# 3020_V1_1.net
KiCad netlist of a schematic drawn in EasyEDA Pro
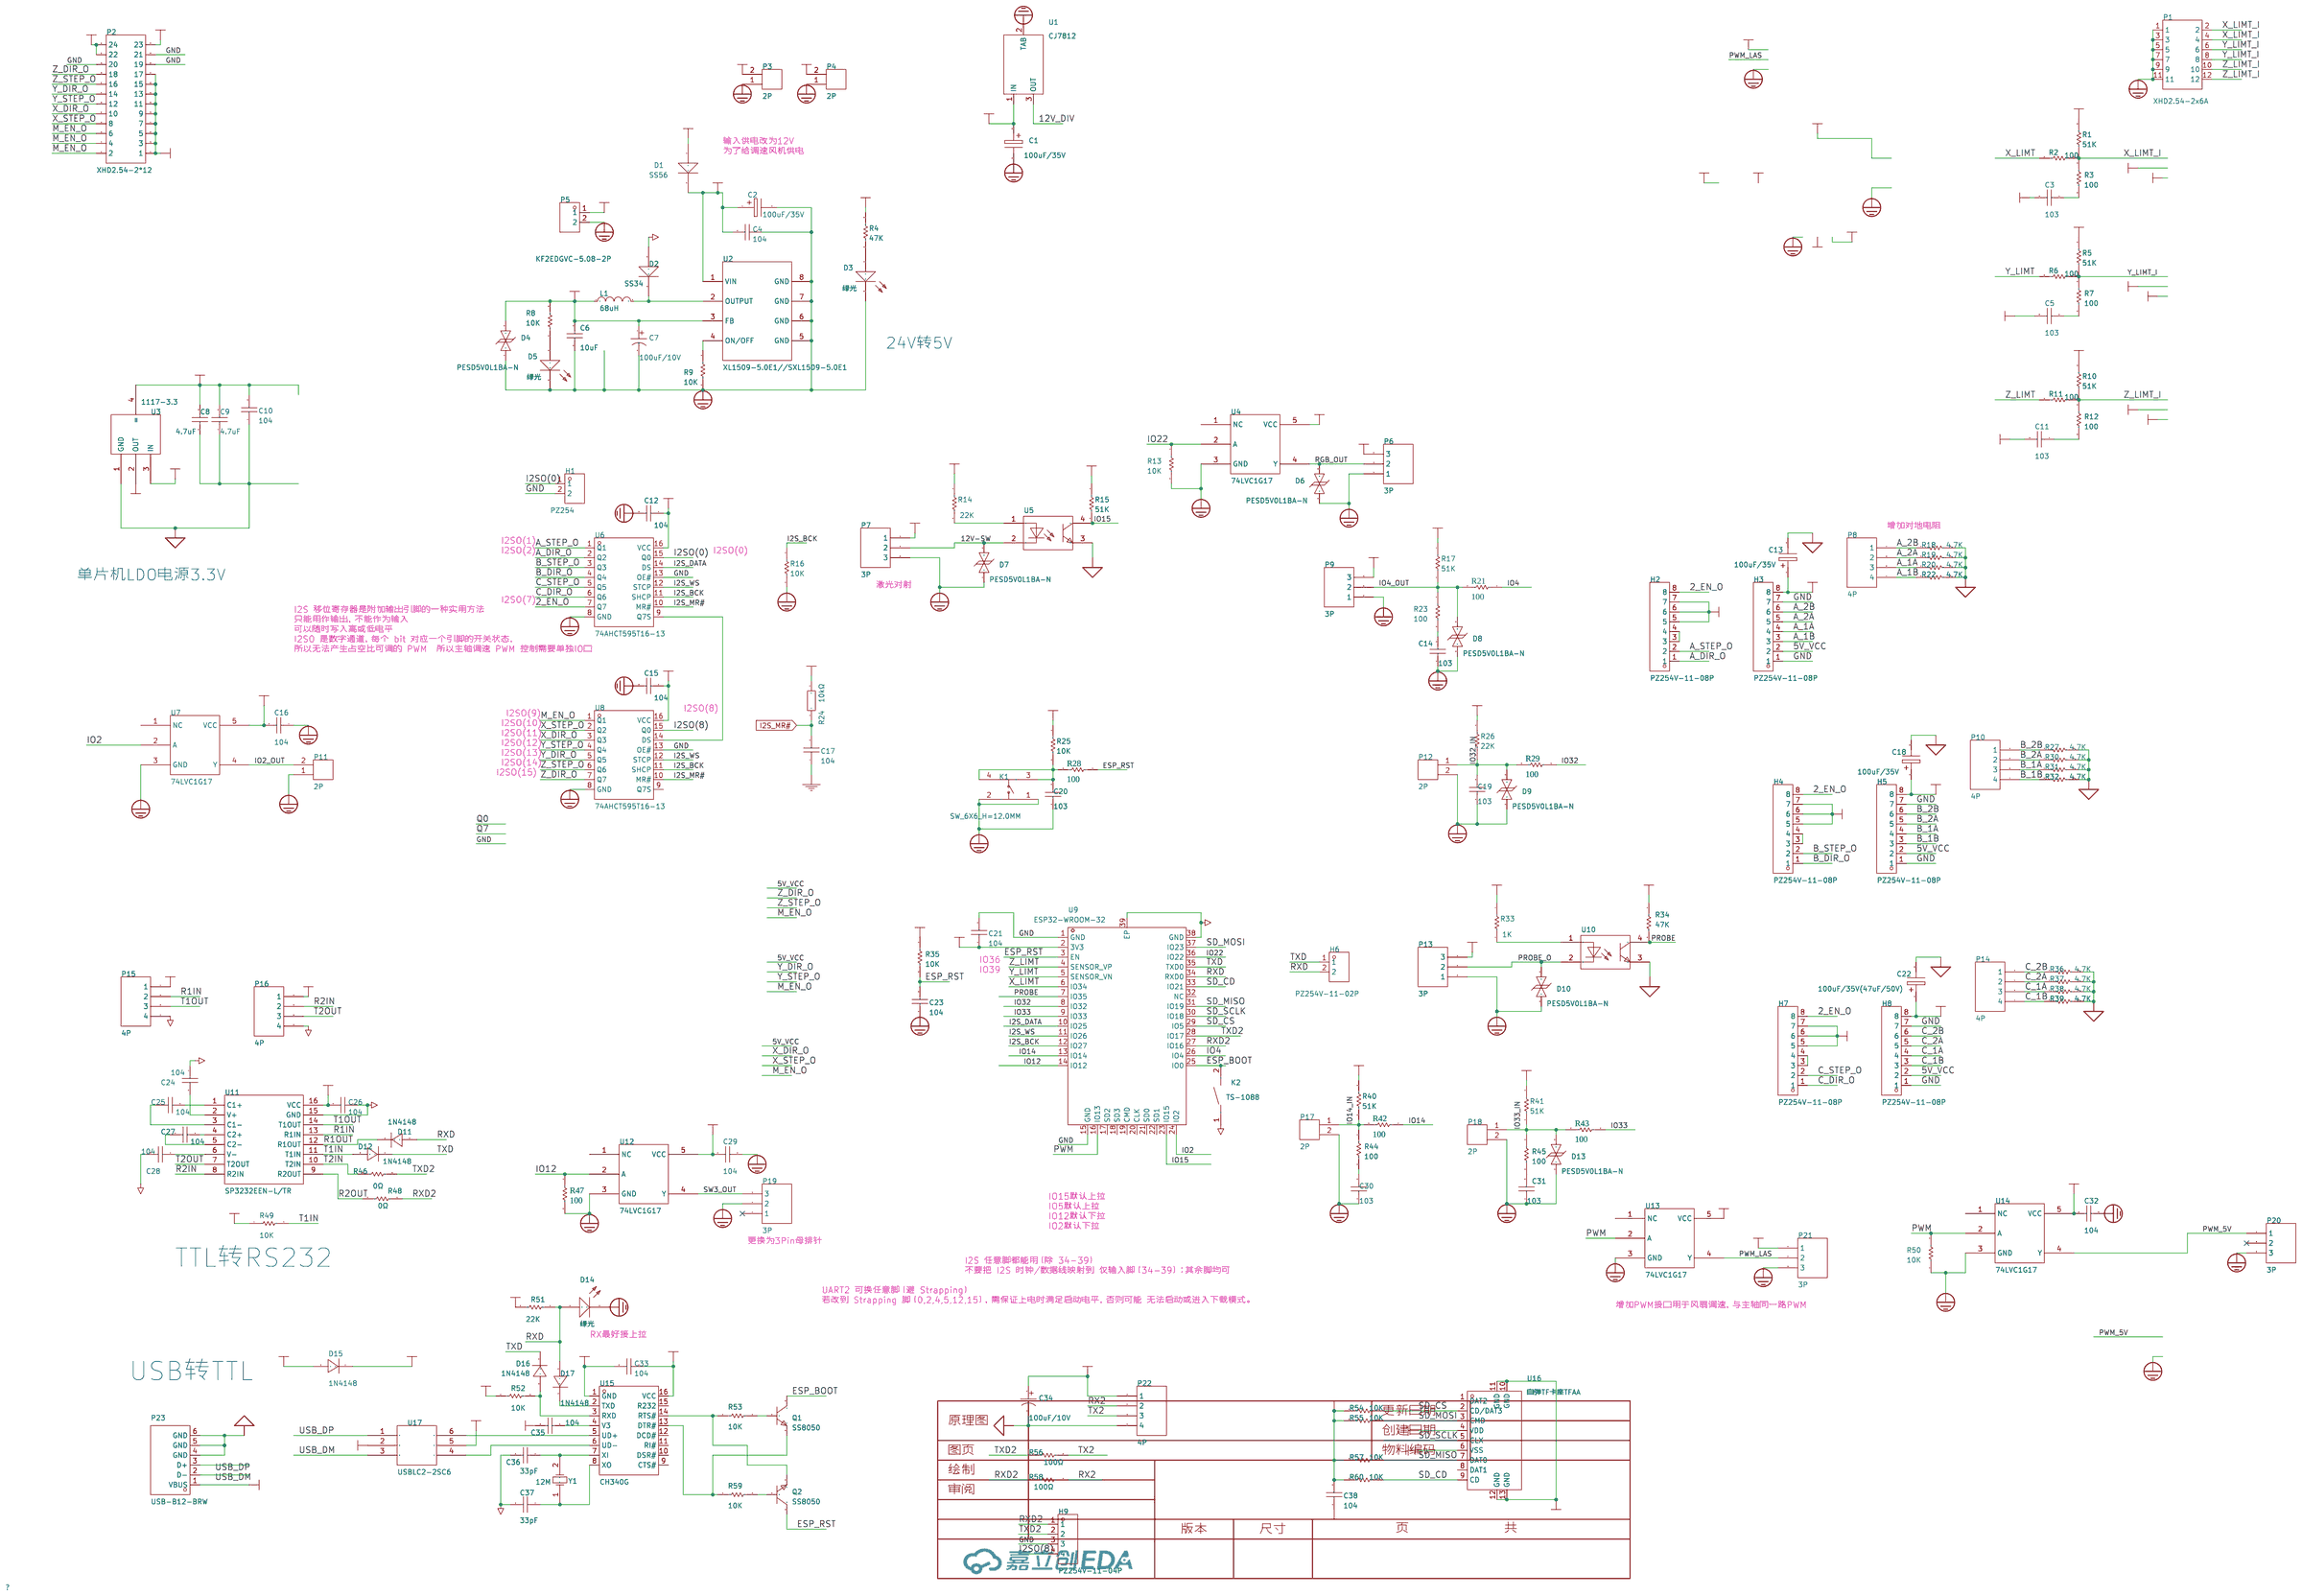
[diagram p0: schematic sheet]

(export (version "E")
  (design (tool "Eeschema 10.0.6"))
  (components
    (comp (ref "C1")
      (value "100uF/35V")
      (footprint "easyedapro:电解电容贴片10x10")
      (libsource (lib "easyedapro") (part "ELECTRO1"))
    )
    (comp (ref "C2")
      (value "100uF/35V")
      (footprint "easyedapro:电解电容贴片10x10")
      (libsource (lib "easyedapro") (part "ELECTRO1"))
    )
    (comp (ref "C3") (value "103") (footprint "easyedapro:11") (libsource (lib "easyedapro") (part "CAP")))
    (comp (ref "C4")
      (value "104")
      (footprint "easyedapro:0603C")
      (description "Capacitor (Semiconductor SIM Model)")
      (libsource (lib "easyedapro") (part "Cap Semi"))
    )
    (comp (ref "C5") (value "103") (footprint "easyedapro:11") (libsource (lib "easyedapro") (part "CAP")))
    (comp (ref "C6") (value "10uF") (libsource (lib "") (part "CAP_1")))
    (comp (ref "C7")
      (value "100uF/10V")
      (footprint "easyedapro:CAP-SMD_BD5.0-L5.3-W5.3-RD")
      (fields (field (name "Manufacturer Part") "CS1A101M-CRD54") (field (name "Manufacturer") "ST(先科)"))
      (libsource (lib "easyedapro") (part "CS1A101M-CRD54"))
    )
    (comp (ref "C8") (value "4.7uF") (libsource (lib "") (part "CAP_1")))
    (comp (ref "C9") (value "4.7uF") (libsource (lib "") (part "CAP_1")))
    (comp (ref "C10")
      (value "104")
      (footprint "easyedapro:0603C")
      (description "Capacitor (Semiconductor SIM Model)")
      (libsource (lib "easyedapro") (part "Cap Semi"))
    )
    (comp (ref "C11") (value "103") (footprint "easyedapro:11") (libsource (lib "easyedapro") (part "CAP")))
    (comp (ref "C12")
      (value "104")
      (footprint "easyedapro:0603C")
      (description "Capacitor (Semiconductor SIM Model)")
      (libsource (lib "easyedapro") (part "Cap Semi"))
    )
    (comp (ref "C13")
      (value "100uF/35V")
      (footprint "easyedapro:电解电容贴片10x10")
      (libsource (lib "easyedapro") (part "ELECTRO1"))
    )
    (comp (ref "C14") (value "103") (footprint "easyedapro:11") (libsource (lib "easyedapro") (part "CAP")))
    (comp (ref "C15")
      (value "104")
      (footprint "easyedapro:0603C")
      (description "Capacitor (Semiconductor SIM Model)")
      (libsource (lib "easyedapro") (part "Cap Semi"))
    )
    (comp (ref "C16")
      (value "104")
      (footprint "easyedapro:0603C")
      (description "Capacitor (Semiconductor SIM Model)")
      (libsource (lib "easyedapro") (part "Cap Semi"))
    )
    (comp (ref "C17")
      (value "104")
      (footprint "easyedapro:0603C")
      (description "Capacitor (Semiconductor SIM Model)")
      (libsource (lib "easyedapro") (part "Cap Semi"))
    )
    (comp (ref "C18")
      (value "100uF/35V")
      (footprint "easyedapro:电解电容贴片10x10")
      (libsource (lib "easyedapro") (part "ELECTRO1"))
    )
    (comp (ref "C19") (value "103") (footprint "easyedapro:11") (libsource (lib "easyedapro") (part "CAP")))
    (comp (ref "C20") (value "103") (footprint "easyedapro:11") (libsource (lib "easyedapro") (part "CAP")))
    (comp (ref "C21")
      (value "104")
      (footprint "easyedapro:0603C")
      (description "Capacitor (Semiconductor SIM Model)")
      (libsource (lib "easyedapro") (part "Cap Semi"))
    )
    (comp (ref "C22")
      (value "100uF/35V(47uF/50V)")
      (footprint "easyedapro:电解电容贴片10x10")
      (libsource (lib "easyedapro") (part "ELECTRO1"))
    )
    (comp (ref "C23")
      (value "104")
      (footprint "easyedapro:0603C")
      (description "Capacitor (Semiconductor SIM Model)")
      (libsource (lib "easyedapro") (part "Cap Semi"))
    )
    (comp (ref "C24")
      (value "104")
      (footprint "easyedapro:0603C")
      (description "Capacitor (Semiconductor SIM Model)")
      (libsource (lib "easyedapro") (part "Cap Semi"))
    )
    (comp (ref "C25")
      (value "104")
      (footprint "easyedapro:0603C")
      (description "Capacitor (Semiconductor SIM Model)")
      (libsource (lib "easyedapro") (part "Cap Semi"))
    )
    (comp (ref "C26")
      (value "104")
      (footprint "easyedapro:0603C")
      (description "Capacitor (Semiconductor SIM Model)")
      (libsource (lib "easyedapro") (part "Cap Semi"))
    )
    (comp (ref "C27")
      (value "104")
      (footprint "easyedapro:0603C")
      (description "Capacitor (Semiconductor SIM Model)")
      (libsource (lib "easyedapro") (part "Cap Semi"))
    )
    (comp (ref "C28")
      (value "104")
      (footprint "easyedapro:0603C")
      (description "Capacitor (Semiconductor SIM Model)")
      (libsource (lib "easyedapro") (part "Cap Semi"))
    )
    (comp (ref "C29")
      (value "104")
      (footprint "easyedapro:0603C")
      (description "Capacitor (Semiconductor SIM Model)")
      (libsource (lib "easyedapro") (part "Cap Semi"))
    )
    (comp (ref "C30") (value "103") (footprint "easyedapro:11") (libsource (lib "easyedapro") (part "CAP")))
    (comp (ref "C31") (value "103") (footprint "easyedapro:11") (libsource (lib "easyedapro") (part "CAP")))
    (comp (ref "C32")
      (value "104")
      (footprint "easyedapro:0603C")
      (description "Capacitor (Semiconductor SIM Model)")
      (libsource (lib "easyedapro") (part "Cap Semi"))
    )
    (comp (ref "C33")
      (value "104")
      (footprint "easyedapro:0603C")
      (description "Capacitor (Semiconductor SIM Model)")
      (libsource (lib "easyedapro") (part "Cap Semi"))
    )
    (comp (ref "C34")
      (value "100uF/10V")
      (footprint "easyedapro:CAP-SMD_BD5.0-L5.3-W5.3-RD")
      (fields (field (name "Manufacturer Part") "CS1A101M-CRD54") (field (name "Manufacturer") "ST(先科)"))
      (libsource (lib "easyedapro") (part "CS1A101M-CRD54"))
    )
    (comp (ref "C35")
      (value "104")
      (footprint "easyedapro:0603C")
      (description "Capacitor (Semiconductor SIM Model)")
      (libsource (lib "easyedapro") (part "Cap Semi"))
    )
    (comp (ref "C36")
      (value "18pF")
      (footprint "easyedapro:0603C")
      (description "Capacitor (Semiconductor SIM Model)")
      (libsource (lib "easyedapro") (part "Cap Semi"))
    )
    (comp (ref "C37")
      (value "18pF")
      (footprint "easyedapro:0603C")
      (description "Capacitor (Semiconductor SIM Model)")
      (libsource (lib "easyedapro") (part "Cap Semi"))
    )
    (comp (ref "C38")
      (value "104")
      (footprint "easyedapro:11")
      (description "Capacitor (Semiconductor SIM Model)")
      (libsource (lib "easyedapro") (part "Cap Semi"))
    )
    (comp (ref "D1") (value "SS56") (footprint "easyedapro:SMA") (libsource (lib "") (part "1N4148_1")))
    (comp (ref "D2") (value "SS34") (libsource (lib "easyedapro") (part "1N4148")))
    (comp (ref "D3")
      (value "绿光")
      (footprint "easyedapro:0603LED")
      (libsource (lib "easyedapro") (part "LED"))
    )
    (comp (ref "D4")
      (value "PESD5V0L1BA-N")
      (footprint "easyedapro:SOD-523_L1.2-W0.8-LS1.6-BI")
      (description "极性:Bidirectional;反向关断电压（典型值）:5V (Max);击穿电压（最小值）:6V;箝位电压:15V;峰值脉冲电流（10/1000us）:5A (8/20us);")
      (fields (field (name "Manufacturer") "BORN伯恩半导体"))
      (libsource (lib "easyedapro") (part "PESD5V0S1BBN"))
    )
    (comp (ref "D5")
      (value "绿光")
      (footprint "easyedapro:0603LED")
      (libsource (lib "easyedapro") (part "LED"))
    )
    (comp (ref "D6")
      (value "PESD5V0L1BA-N")
      (footprint "easyedapro:SOD-523_L1.2-W0.8-LS1.6-BI")
      (description "极性:Bidirectional;反向关断电压（典型值）:5V (Max);击穿电压（最小值）:6V;箝位电压:15V;峰值脉冲电流（10/1000us）:5A (8/20us);")
      (fields (field (name "Manufacturer") "BORN伯恩半导体"))
      (libsource (lib "easyedapro") (part "PESD5V0S1BBN"))
    )
    (comp (ref "D7")
      (value "PESD5V0L1BA-N")
      (footprint "easyedapro:SOD-523_L1.2-W0.8-LS1.6-BI")
      (description "极性:Bidirectional;反向关断电压（典型值）:5V (Max);击穿电压（最小值）:6V;箝位电压:15V;峰值脉冲电流（10/1000us）:5A (8/20us);")
      (fields (field (name "Manufacturer") "BORN伯恩半导体"))
      (libsource (lib "easyedapro") (part "PESD5V0S1BBN"))
    )
    (comp (ref "D8")
      (value "PESD5V0L1BA-N")
      (footprint "easyedapro:SOD-523_L1.2-W0.8-LS1.6-BI")
      (description "极性:Bidirectional;反向关断电压（典型值）:5V (Max);击穿电压（最小值）:6V;箝位电压:15V;峰值脉冲电流（10/1000us）:5A (8/20us);")
      (fields (field (name "Manufacturer") "BORN伯恩半导体"))
      (libsource (lib "easyedapro") (part "PESD5V0S1BBN"))
    )
    (comp (ref "D9")
      (value "PESD5V0L1BA-N")
      (footprint "easyedapro:SOD-523_L1.2-W0.8-LS1.6-BI")
      (description "极性:Bidirectional;反向关断电压（典型值）:5V (Max);击穿电压（最小值）:6V;箝位电压:15V;峰值脉冲电流（10/1000us）:5A (8/20us);")
      (fields (field (name "Manufacturer") "BORN伯恩半导体"))
      (libsource (lib "easyedapro") (part "PESD5V0S1BBN"))
    )
    (comp (ref "D10")
      (value "PESD5V0L1BA-N")
      (footprint "easyedapro:SOD-523_L1.2-W0.8-LS1.6-BI")
      (description "极性:Bidirectional;反向关断电压（典型值）:5V (Max);击穿电压（最小值）:6V;箝位电压:15V;峰值脉冲电流（10/1000us）:5A (8/20us);")
      (fields (field (name "Manufacturer") "BORN伯恩半导体"))
      (libsource (lib "easyedapro") (part "PESD5V0S1BBN"))
    )
    (comp (ref "D11")
      (value "1N4148")
      (footprint "easyedapro:SOD-123_L2.8-W1.8-LS3.7-RD")
      (fields (field (name "Manufacturer") "VISHAY(威世)"))
      (libsource (lib "easyedapro") (part "1N4148W-E3-08"))
    )
    (comp (ref "D12")
      (value "1N4148")
      (footprint "easyedapro:SOD-123_L2.8-W1.8-LS3.7-RD")
      (fields (field (name "Manufacturer") "VISHAY(威世)"))
      (libsource (lib "easyedapro") (part "1N4148W-E3-08"))
    )
    (comp (ref "D13")
      (value "PESD5V0L1BA-N")
      (footprint "easyedapro:SOD-523_L1.2-W0.8-LS1.6-BI")
      (description "极性:Bidirectional;反向关断电压（典型值）:5V (Max);击穿电压（最小值）:6V;箝位电压:15V;峰值脉冲电流（10/1000us）:5A (8/20us);")
      (fields (field (name "Manufacturer") "BORN伯恩半导体"))
      (libsource (lib "easyedapro") (part "PESD5V0S1BBN"))
    )
    (comp (ref "D14")
      (value "绿光")
      (footprint "easyedapro:0603LED")
      (libsource (lib "easyedapro") (part "LED"))
    )
    (comp (ref "D15")
      (value "1N4148")
      (footprint "easyedapro:SOD-123_L2.8-W1.8-LS3.7-RD")
      (fields (field (name "Manufacturer") "VISHAY(威世)"))
      (libsource (lib "easyedapro") (part "1N4148W-E3-08"))
    )
    (comp (ref "D16")
      (value "1N4148")
      (footprint "easyedapro:SOD-123_L2.8-W1.8-LS3.7-RD")
      (fields (field (name "Manufacturer") "VISHAY(威世)"))
      (libsource (lib "easyedapro") (part "1N4148W-E3-08"))
    )
    (comp (ref "D17")
      (value "1N4148")
      (footprint "easyedapro:SOD-123_L2.8-W1.8-LS3.7-RD")
      (fields (field (name "Manufacturer") "VISHAY(威世)"))
      (libsource (lib "easyedapro") (part "1N4148W-E3-08"))
    )
    (comp (ref "H1")
      (value "PZ254")
      (footprint "easyedapro:HDR-TH_2P-P2.54-V-M")
      (fields (field (name "Manufacturer") "XFCN(兴飞)"))
      (libsource (lib "easyedapro") (part "PZ254V-11-02P"))
    )
    (comp (ref "H2")
      (value "PZ254V-11-08P")
      (footprint "easyedapro:HDR-TH_8P-P2.54-V-M")
      (fields (field (name "Manufacturer") "XFCN(兴飞)"))
      (libsource (lib "easyedapro") (part "PZ254V-11-08P"))
    )
    (comp (ref "H3")
      (value "PZ254V-11-08P")
      (footprint "easyedapro:HDR-TH_8P-P2.54-V-M")
      (fields (field (name "Manufacturer") "XFCN(兴飞)"))
      (libsource (lib "easyedapro") (part "PZ254V-11-08P"))
    )
    (comp (ref "H4")
      (value "PZ254V-11-08P")
      (footprint "easyedapro:HDR-TH_8P-P2.54-V-M")
      (fields (field (name "Manufacturer") "XFCN(兴飞)"))
      (libsource (lib "easyedapro") (part "PZ254V-11-08P"))
    )
    (comp (ref "H5")
      (value "PZ254V-11-08P")
      (footprint "easyedapro:HDR-TH_8P-P2.54-V-M")
      (fields (field (name "Manufacturer") "XFCN(兴飞)"))
      (libsource (lib "easyedapro") (part "PZ254V-11-08P"))
    )
    (comp (ref "H6")
      (value "PZ254V-11-02P")
      (footprint "easyedapro:HDR-TH_2P-P2.54-V-M")
      (fields (field (name "Manufacturer") "XFCN(兴飞)"))
      (libsource (lib "easyedapro") (part "PZ254V-11-02P"))
    )
    (comp (ref "H7")
      (value "PZ254V-11-08P")
      (footprint "easyedapro:HDR-TH_8P-P2.54-V-M")
      (fields (field (name "Manufacturer") "XFCN(兴飞)"))
      (libsource (lib "easyedapro") (part "PZ254V-11-08P"))
    )
    (comp (ref "H8")
      (value "PZ254V-11-08P")
      (footprint "easyedapro:HDR-TH_8P-P2.54-V-M")
      (fields (field (name "Manufacturer") "XFCN(兴飞)"))
      (libsource (lib "easyedapro") (part "PZ254V-11-08P"))
    )
    (comp (ref "H9")
      (value "PZ254V-11-04P")
      (footprint "easyedapro:HDR-TH_4P-P2.54-V-M")
      (fields (field (name "Manufacturer") "XFCN(兴飞)"))
      (libsource (lib "easyedapro") (part "PZ254V-11-04P_C2691448"))
    )
    (comp (ref "K1")
      (value "SW_6X6_H=12.0MM")
      (footprint "easyedapro:KEY-SMD_4P-L6.0-W6.0-P4.50-LS9.0")
      (libsource (lib "easyedapro") (part "SW_6X6_H=12.0MM"))
    )
    (comp (ref "K2")
      (value "TS-1088")
      (footprint "easyedapro:SW-SMD_L3.9-W3.0-P4.45")
      (fields (field (name "Manufacturer") "XUNPU(讯普)"))
      (libsource (lib "easyedapro") (part "TS-1088-AR02016"))
    )
    (comp (ref "L1")
      (value "68uH")
      (footprint "easyedapro:IND-SMD_L7.0-W7.0_SMDRI74-330MT")
      (description "电感值:33uH;精度:±20%;额定电流:960mA;饱和电流(Isat):1.8A;类型:屏蔽电感;")
      (fields (field (name "Manufacturer Part") "SMDRI74-330MT") (field (name "Manufacturer") "SXN(顺翔诺)"))
      (libsource (lib "easyedapro") (part "SMDRI74-330MT"))
    )
    (comp (ref "P1")
      (value "XHD2.54-2x6A")
      (footprint "easyedapro:CONN-TH_12P-P2.50_HC-XHD2.54-2X6A")
      (fields (field (name "Manufacturer") "HC(虹成电子)"))
      (libsource (lib "easyedapro") (part "HC-XHD2.54-2X6A"))
    )
    (comp (ref "P2")
      (value "XHD2.54-2*12")
      (footprint "easyedapro:IDC-TH_24P-P2.54-V-R2-C12-S2.54")
      (fields (field (name "Manufacturer") "BOOMELE(博穆精密)"))
      (libsource (lib "easyedapro") (part "HDR-IDC-2.54-2X12P"))
    )
    (comp (ref "P3") (value "2P") (libsource (lib "easyedapro") (part "2P")))
    (comp (ref "P4") (value "2P") (libsource (lib "easyedapro") (part "2P")))
    (comp (ref "P5")
      (value "KF2EDGVC-5.08-2P")
      (footprint "easyedapro:CONN-TH_P5.08_KF2EDGVC-5.08-2P")
      (description "连接器类型:板端/插座-闭口;结构:1x2P;间距:5.08mm;颜色:绿色;安装方式:直针;排数:1;每排PIN数:2;额定电流:15A;额定电压:300V;工作温度:-40°C~+105°C;")
      (fields (field (name "Manufacturer") "KEFA(科发)"))
      (libsource (lib "easyedapro") (part "KF2EDGVC-5.08-2P"))
    )
    (comp (ref "P6")
      (value "3P")
      (footprint "easyedapro:HDR1X3_CON")
      (libsource (lib "easyedapro") (part "3P"))
    )
    (comp (ref "P7")
      (value "3P")
      (footprint "easyedapro:HDR1X3_CON")
      (libsource (lib "easyedapro") (part "3P"))
    )
    (comp (ref "P8")
      (value "4P")
      (footprint "easyedapro:HDR1X4_CON")
      (libsource (lib "easyedapro") (part "4P"))
    )
    (comp (ref "P9")
      (value "3P")
      (footprint "easyedapro:HDR1X3_CON")
      (libsource (lib "easyedapro") (part "3P"))
    )
    (comp (ref "P10")
      (value "4P")
      (footprint "easyedapro:HDR1X4_CON")
      (libsource (lib "easyedapro") (part "4P"))
    )
    (comp (ref "P11") (value "2P") (libsource (lib "easyedapro") (part "2P")))
    (comp (ref "P12") (value "2P") (libsource (lib "easyedapro") (part "2P")))
    (comp (ref "P13")
      (value "3P")
      (footprint "easyedapro:HDR1X3_CON")
      (libsource (lib "easyedapro") (part "3P"))
    )
    (comp (ref "P14")
      (value "4P")
      (footprint "easyedapro:HDR1X4_CON")
      (libsource (lib "easyedapro") (part "4P"))
    )
    (comp (ref "P15")
      (value "4P")
      (footprint "easyedapro:HDR1X4_CON")
      (libsource (lib "easyedapro") (part "4P"))
    )
    (comp (ref "P16")
      (value "4P")
      (footprint "easyedapro:HDR1X4_CON")
      (libsource (lib "easyedapro") (part "4P"))
    )
    (comp (ref "P17") (value "2P") (libsource (lib "easyedapro") (part "2P")))
    (comp (ref "P18") (value "2P") (libsource (lib "easyedapro") (part "2P")))
    (comp (ref "P19")
      (value "3P")
      (footprint "easyedapro:HDR1X3_CON")
      (libsource (lib "easyedapro") (part "3P"))
    )
    (comp (ref "P20")
      (value "3P")
      (footprint "easyedapro:HDR1X3_CON")
      (libsource (lib "easyedapro") (part "3P"))
    )
    (comp (ref "P21")
      (value "3P")
      (footprint "easyedapro:HDR1X3_CON")
      (libsource (lib "easyedapro") (part "3P"))
    )
    (comp (ref "P22")
      (value "4P")
      (footprint "easyedapro:HDR1X4_CON")
      (libsource (lib "easyedapro") (part "4P"))
    )
    (comp (ref "P23")
      (value "USB-B12-BRW")
      (footprint "easyedapro:USB-B-TH_USB-B12-BRW")
      (description "连接器类型:Type-B;协议标准:USB 2.0;公母:母;安装方式:直插;触点数量:4P;端口数量:1;额定电流 - 电源:1.5A;工作温度:-20°C~+70°C;")
      (fields (field (name "Manufacturer") "XUNPU(讯普)"))
      (libsource (lib "easyedapro") (part "USB-B12-BRW"))
    )
    (comp (ref "Q1")
      (value "SS8050")
      (footprint "easyedapro:SOT-23-3_L2.9-W1.3-P1.90-LS2.4-BR")
      (fields (field (name "Manufacturer") "Doeshare(德芯)"))
      (libsource (lib "easyedapro") (part "SS8050_C2931717"))
    )
    (comp (ref "Q2")
      (value "SS8050")
      (footprint "easyedapro:SOT-23-3_L2.9-W1.3-P1.90-LS2.4-BR")
      (fields (field (name "Manufacturer") "Doeshare(德芯)"))
      (libsource (lib "easyedapro") (part "SS8050_C2931717"))
    )
    (comp (ref "R1")
      (value "51K")
      (footprint "easyedapro:10")
      (description "Resistor")
      (libsource (lib "easyedapro") (part "RES"))
    )
    (comp (ref "R2")
      (value "100")
      (footprint "easyedapro:10")
      (description "Resistor")
      (libsource (lib "easyedapro") (part "RES"))
    )
    (comp (ref "R3")
      (value "100")
      (footprint "easyedapro:10")
      (description "Resistor")
      (libsource (lib "easyedapro") (part "RES"))
    )
    (comp (ref "R4")
      (value "47K")
      (footprint "easyedapro:0603R")
      (description "Resistor")
      (libsource (lib "easyedapro") (part "RES"))
    )
    (comp (ref "R5")
      (value "51K")
      (footprint "easyedapro:10")
      (description "Resistor")
      (libsource (lib "easyedapro") (part "RES"))
    )
    (comp (ref "R6")
      (value "100")
      (footprint "easyedapro:10")
      (description "Resistor")
      (libsource (lib "easyedapro") (part "RES"))
    )
    (comp (ref "R7")
      (value "100")
      (footprint "easyedapro:10")
      (description "Resistor")
      (libsource (lib "easyedapro") (part "RES"))
    )
    (comp (ref "R8")
      (value "10K")
      (footprint "easyedapro:0603R")
      (description "Resistor")
      (libsource (lib "easyedapro") (part "RES"))
    )
    (comp (ref "R9")
      (value "10K")
      (footprint "easyedapro:0603R")
      (description "Resistor")
      (libsource (lib "easyedapro") (part "RES"))
    )
    (comp (ref "R10")
      (value "51K")
      (footprint "easyedapro:10")
      (description "Resistor")
      (libsource (lib "easyedapro") (part "RES"))
    )
    (comp (ref "R11")
      (value "100")
      (footprint "easyedapro:10")
      (description "Resistor")
      (libsource (lib "easyedapro") (part "RES"))
    )
    (comp (ref "R12")
      (value "100")
      (footprint "easyedapro:10")
      (description "Resistor")
      (libsource (lib "easyedapro") (part "RES"))
    )
    (comp (ref "R13")
      (value "10K")
      (description "Resistor")
      (fields (field (name "Publisher") "Altium Limited"))
      (libsource (lib "") (part "RES_1"))
    )
    (comp (ref "R14")
      (value "22K")
      (footprint "easyedapro:0603R")
      (description "Resistor")
      (libsource (lib "easyedapro") (part "RES"))
    )
    (comp (ref "R15")
      (value "10K")
      (footprint "easyedapro:0603R")
      (description "Resistor")
      (libsource (lib "easyedapro") (part "RES"))
    )
    (comp (ref "R16")
      (value "10K")
      (footprint "easyedapro:0603R")
      (description "Resistor")
      (libsource (lib "easyedapro") (part "RES"))
    )
    (comp (ref "R17")
      (value "10K")
      (footprint "easyedapro:0603R")
      (description "Resistor")
      (libsource (lib "easyedapro") (part "RES"))
    )
    (comp (ref "R18")
      (value "10K")
      (footprint "easyedapro:0603R")
      (description "Resistor")
      (libsource (lib "easyedapro") (part "10K"))
    )
    (comp (ref "R19")
      (value "10K")
      (footprint "easyedapro:0603R")
      (description "Resistor")
      (libsource (lib "easyedapro") (part "10K"))
    )
    (comp (ref "R20")
      (value "10K")
      (footprint "easyedapro:0603R")
      (description "Resistor")
      (libsource (lib "easyedapro") (part "10K"))
    )
    (comp (ref "R21")
      (value "100")
      (description "Resistor")
      (fields (field (name "Publisher") "Altium Limited"))
      (libsource (lib "") (part "RES_1"))
    )
    (comp (ref "R22")
      (value "10K")
      (footprint "easyedapro:0603R")
      (description "Resistor")
      (libsource (lib "easyedapro") (part "10K"))
    )
    (comp (ref "R23")
      (value "100")
      (footprint "easyedapro:10")
      (description "Resistor")
      (libsource (lib "easyedapro") (part "RES"))
    )
    (comp (ref "R24")
      (value "10kΩ")
      (footprint "easyedapro:R0603")
      (fields (field (name "Manufacturer Part") "0603WAF1002T5E") (field (name "Manufacturer") "UniOhm"))
      (libsource (lib "easyedapro") (part "10kΩ"))
    )
    (comp (ref "R25")
      (value "10K")
      (footprint "easyedapro:0603R")
      (description "Resistor")
      (libsource (lib "easyedapro") (part "RES"))
    )
    (comp (ref "R26")
      (value "10K")
      (footprint "easyedapro:0603R")
      (description "Resistor")
      (libsource (lib "easyedapro") (part "RES"))
    )
    (comp (ref "R27")
      (value "10K")
      (footprint "easyedapro:0603R")
      (description "Resistor")
      (libsource (lib "easyedapro") (part "10K"))
    )
    (comp (ref "R28")
      (value "100")
      (description "Resistor")
      (fields (field (name "Publisher") "Altium Limited"))
      (libsource (lib "") (part "RES_1"))
    )
    (comp (ref "R29")
      (value "100")
      (description "Resistor")
      (fields (field (name "Publisher") "Altium Limited"))
      (libsource (lib "") (part "RES_1"))
    )
    (comp (ref "R30")
      (value "10K")
      (footprint "easyedapro:0603R")
      (description "Resistor")
      (libsource (lib "easyedapro") (part "10K"))
    )
    (comp (ref "R31")
      (value "10K")
      (footprint "easyedapro:0603R")
      (description "Resistor")
      (libsource (lib "easyedapro") (part "10K"))
    )
    (comp (ref "R32")
      (value "10K")
      (footprint "easyedapro:0603R")
      (description "Resistor")
      (libsource (lib "easyedapro") (part "10K"))
    )
    (comp (ref "R33")
      (value "1K")
      (footprint "easyedapro:0603R")
      (description "Resistor")
      (libsource (lib "easyedapro") (part "RES"))
    )
    (comp (ref "R34")
      (value "10K")
      (footprint "easyedapro:0603R")
      (description "Resistor")
      (libsource (lib "easyedapro") (part "RES"))
    )
    (comp (ref "R35")
      (value "10K")
      (footprint "easyedapro:0603R")
      (description "Resistor")
      (libsource (lib "easyedapro") (part "RES"))
    )
    (comp (ref "R36")
      (value "10K")
      (footprint "easyedapro:0603R")
      (description "Resistor")
      (libsource (lib "easyedapro") (part "10K"))
    )
    (comp (ref "R37")
      (value "10K")
      (footprint "easyedapro:0603R")
      (description "Resistor")
      (libsource (lib "easyedapro") (part "10K"))
    )
    (comp (ref "R38")
      (value "10K")
      (footprint "easyedapro:0603R")
      (description "Resistor")
      (libsource (lib "easyedapro") (part "10K"))
    )
    (comp (ref "R39")
      (value "10K")
      (footprint "easyedapro:0603R")
      (description "Resistor")
      (libsource (lib "easyedapro") (part "10K"))
    )
    (comp (ref "R40")
      (value "10K")
      (footprint "easyedapro:0603R")
      (description "Resistor")
      (libsource (lib "easyedapro") (part "RES"))
    )
    (comp (ref "R41")
      (value "10K")
      (footprint "easyedapro:0603R")
      (description "Resistor")
      (libsource (lib "easyedapro") (part "RES"))
    )
    (comp (ref "R42")
      (value "100")
      (description "Resistor")
      (fields (field (name "Publisher") "Altium Limited"))
      (libsource (lib "") (part "RES_1"))
    )
    (comp (ref "R43")
      (value "100")
      (description "Resistor")
      (fields (field (name "Publisher") "Altium Limited"))
      (libsource (lib "") (part "RES_1"))
    )
    (comp (ref "R44")
      (value "100")
      (footprint "easyedapro:10")
      (description "Resistor")
      (libsource (lib "easyedapro") (part "RES"))
    )
    (comp (ref "R45")
      (value "100")
      (footprint "easyedapro:10")
      (description "Resistor")
      (libsource (lib "easyedapro") (part "RES"))
    )
    (comp (ref "R46")
      (value "0Ω")
      (footprint "easyedapro:0603R")
      (description "Resistor")
      (libsource (lib "easyedapro") (part "RES"))
    )
    (comp (ref "R47")
      (value "100")
      (description "Resistor")
      (fields (field (name "Publisher") "Altium Limited"))
      (libsource (lib "") (part "RES_1"))
    )
    (comp (ref "R48")
      (value "0Ω")
      (footprint "easyedapro:0603R")
      (description "Resistor")
      (libsource (lib "easyedapro") (part "RES"))
    )
    (comp (ref "R49")
      (value "10K")
      (footprint "easyedapro:0603R")
      (description "Resistor")
      (libsource (lib "easyedapro") (part "RES"))
    )
    (comp (ref "R50")
      (value "10K")
      (description "Resistor")
      (fields (field (name "Publisher") "Altium Limited"))
      (libsource (lib "") (part "RES_1"))
    )
    (comp (ref "R51")
      (value "10K")
      (footprint "easyedapro:0603R")
      (description "Resistor")
      (libsource (lib "easyedapro") (part "RES"))
    )
    (comp (ref "R52")
      (value "10K")
      (footprint "easyedapro:0603R")
      (description "Resistor")
      (libsource (lib "easyedapro") (part "RES"))
    )
    (comp (ref "R53")
      (value "10K")
      (footprint "easyedapro:0603R")
      (description "Resistor")
      (libsource (lib "easyedapro") (part "RES"))
    )
    (comp (ref "R54")
      (value "10K")
      (footprint "easyedapro:10")
      (description "Resistor")
      (libsource (lib "easyedapro") (part "RES"))
    )
    (comp (ref "R55")
      (value "10K")
      (footprint "easyedapro:10")
      (description "Resistor")
      (libsource (lib "easyedapro") (part "RES"))
    )
    (comp (ref "R56")
      (value "100Ω")
      (footprint "easyedapro:0603R")
      (description "Resistor")
      (libsource (lib "easyedapro") (part "RES"))
    )
    (comp (ref "R57")
      (value "10K")
      (footprint "easyedapro:10")
      (description "Resistor")
      (libsource (lib "easyedapro") (part "RES"))
    )
    (comp (ref "R58")
      (value "100Ω")
      (footprint "easyedapro:0603R")
      (description "Resistor")
      (libsource (lib "easyedapro") (part "RES"))
    )
    (comp (ref "R59")
      (value "10K")
      (footprint "easyedapro:0603R")
      (description "Resistor")
      (libsource (lib "easyedapro") (part "RES"))
    )
    (comp (ref "R60")
      (value "10K")
      (footprint "easyedapro:10")
      (description "Resistor")
      (libsource (lib "easyedapro") (part "RES"))
    )
    (comp (ref "U1")
      (value "CJ7812")
      (footprint "easyedapro:TO-263-2_L10.1-W9.1-P5.08-LS15.2-TL")
      (description "输出类型:固定;工作电压:35V;输出电压:12V;输出电流:1.5A;电源纹波抑制比(PSRR):71dB@(120Hz);输出极性:正极;")
      (fields (field (name "Manufacturer") "CJ(江苏长电/长晶)"))
      (libsource (lib "easyedapro") (part "CJ7812_C145151"))
    )
    (comp (ref "U2")
      (value "XL1509-5.0E1//SXL1509-5.0E1")
      (footprint "easyedapro:SOIC-8_L5.0-W4.0-P1.27-LS6.0-BL")
      (description "功能类型:降压型;同步整流:-;输出通道数:-;拓扑结构:-;输入电压:-;输出电流(最大值):-;开关频率:-;")
      (fields (field (name "Manufacturer") "XLSEMI(芯龙)"))
      (libsource (lib "easyedapro") (part "XL1509-5.0E1"))
    )
    (comp (ref "U3")
      (value "1117-3.3")
      (footprint "easyedapro:SOT-223")
      (libsource (lib "easyedapro") (part "LM1117"))
    )
    (comp (ref "U4")
      (value "74LVC1G17")
      (footprint "easyedapro:SMD8")
      (libsource (lib "easyedapro") (part "74LVC1G04"))
    )
    (comp (ref "U5")
      (value "LTV-357T-C")
      (footprint "easyedapro:SOP-4_L4.4-W3.9-P2.54-LS7.0-TL")
      (fields (field (name "Manufacturer") "LITEON(光宝)"))
      (libsource (lib "easyedapro") (part "LTV-357T-C"))
    )
    (comp (ref "U6")
      (value "74AHCT595T16-13")
      (footprint "easyedapro:TSSOP-16_L5.0-W4.4-P0.65-LS6.4-BL")
      (description "功能:串行至串行或并行;工作电压:4.5V~5.5V;元件数:1;每个元件位数:8;")
      (fields (field (name "Manufacturer") "DIODES(美台)"))
      (libsource (lib "easyedapro") (part "74AHCT595T16-13"))
    )
    (comp (ref "U7")
      (value "74LVC1G17")
      (footprint "easyedapro:SMD8")
      (libsource (lib "easyedapro") (part "74LVC1G04"))
    )
    (comp (ref "U8")
      (value "74AHCT595T16-13")
      (footprint "easyedapro:TSSOP-16_L5.0-W4.4-P0.65-LS6.4-BL")
      (description "功能:串行至串行或并行;工作电压:4.5V~5.5V;元件数:1;每个元件位数:8;")
      (fields (field (name "Manufacturer") "DIODES(美台)"))
      (libsource (lib "easyedapro") (part "74AHCT595T16-13"))
    )
    (comp (ref "U9")
      (value "ESP32-WROOM-32")
      (footprint "easyedapro:WIFIM-SMD_ESP-WROOM-32")
      (description "WiFi+双模蓝牙 双核CPU 网口 顶配MCU 低功耗蓝牙 ESP32系列ESP-WROOM-32模组/ESP-32S 4MB")
      (fields (field (name "Manufacturer") "ESPRESSIF(乐鑫)"))
      (libsource (lib "easyedapro") (part "ESP-WROOM-32"))
    )
    (comp (ref "U10")
      (value "LTV-357T-C")
      (footprint "easyedapro:SOP-4_L4.4-W3.9-P2.54-LS7.0-TL")
      (fields (field (name "Manufacturer") "LITEON(光宝)"))
      (libsource (lib "easyedapro") (part "LTV-357T-C"))
    )
    (comp (ref "U11")
      (value "SP3232EEN-L/TR")
      (footprint "easyedapro:SOIC-16_L9.9-W3.9-P1.27-LS6.0-BL")
      (description "类型:收发器;数据速率:235Kbps;")
      (fields (field (name "Manufacturer") "MaxLinear(迈凌)"))
      (libsource (lib "easyedapro") (part "SP3232EEN-L/TR"))
    )
    (comp (ref "U12")
      (value "74LVC1G17")
      (footprint "easyedapro:SMD8")
      (libsource (lib "easyedapro") (part "74LVC1G04"))
    )
    (comp (ref "U13")
      (value "74LVC1G17")
      (footprint "easyedapro:SMD8")
      (libsource (lib "easyedapro") (part "74LVC1G04"))
    )
    (comp (ref "U14")
      (value "74LVC1G17")
      (footprint "easyedapro:SMD8")
      (libsource (lib "easyedapro") (part "74LVC1G04"))
    )
    (comp (ref "U15")
      (value "CH340G")
      (footprint "easyedapro:SOIC-16_L9.9-W3.9-P1.27-LS6.0-BL")
      (description "应用功能:收发器;接口协议:USB 2.0;数据速率:2Mbps;")
      (fields (field (name "Manufacturer") "WCH(南京沁恒)"))
      (libsource (lib "easyedapro") (part "CH340G"))
    )
    (comp (ref "U16")
      (value "自弹TF卡座TFAA")
      (footprint "easyedapro:SIM-SMD_C9900015645")
      (libsource (lib "easyedapro") (part "自弹TF卡座TFAA"))
    )
    (comp (ref "U17")
      (value "USBLC2-2SC6")
      (footprint "easyedapro:SOT-23-6")
      (libsource (lib "easyedapro") (part "DIP6"))
    )
    (comp (ref "Y1")
      (value "12M")
      (footprint "easyedapro:晶振贴片49SSMD")
      (description "Crystal Oscillator")
      (libsource (lib "easyedapro") (part "XTAL"))
    )
  )
  (nets
    (net (code "1") (name "/2_EN_O") (class "Default")
      (node (ref "H2") (pin "8") (pinfunction "8_8") (pintype "unspecified"))
      (node (ref "H4") (pin "8") (pinfunction "8_8") (pintype "unspecified"))
      (node (ref "H7") (pin "8") (pinfunction "8_8") (pintype "unspecified"))
      (node (ref "U6") (pin "7") (pinfunction "Q7_7") (pintype "unspecified"))
    )
    (net (code "2") (name "/12V-SW") (class "Default")
      (node (ref "D7") (pin "2") (pinfunction "2_2") (pintype "input"))
      (node (ref "P7") (pin "2") (pinfunction "2_2") (pintype "unspecified"))
      (node (ref "U5") (pin "2") (pinfunction "2_2") (pintype "unspecified"))
    )
    (net (code "3") (name "/A_1A") (class "Default")
      (node (ref "H3") (pin "4") (pinfunction "4_4") (pintype "unspecified"))
      (node (ref "P8") (pin "3") (pinfunction "3_3") (pintype "unspecified"))
      (node (ref "R20") (pin "1") (pinfunction "1_1") (pintype "unspecified"))
    )
    (net (code "4") (name "/A_1B") (class "Default")
      (node (ref "H3") (pin "3") (pinfunction "3_3") (pintype "unspecified"))
      (node (ref "P8") (pin "4") (pinfunction "4_4") (pintype "unspecified"))
      (node (ref "R22") (pin "1") (pinfunction "1_1") (pintype "unspecified"))
    )
    (net (code "5") (name "/A_2A") (class "Default")
      (node (ref "H3") (pin "5") (pinfunction "5_5") (pintype "unspecified"))
      (node (ref "P8") (pin "2") (pinfunction "2_2") (pintype "unspecified"))
      (node (ref "R19") (pin "1") (pinfunction "1_1") (pintype "unspecified"))
    )
    (net (code "6") (name "/A_2B") (class "Default")
      (node (ref "H3") (pin "6") (pinfunction "6_6") (pintype "unspecified"))
      (node (ref "P8") (pin "1") (pinfunction "1_1") (pintype "unspecified"))
      (node (ref "R18") (pin "1") (pinfunction "1_1") (pintype "unspecified"))
    )
    (net (code "7") (name "/A_DIR_O") (class "Default")
      (node (ref "H2") (pin "1") (pinfunction "1_1") (pintype "unspecified"))
      (node (ref "U6") (pin "2") (pinfunction "Q2_2") (pintype "unspecified"))
    )
    (net (code "8") (name "/A_STEP_O") (class "Default")
      (node (ref "H2") (pin "2") (pinfunction "2_2") (pintype "unspecified"))
      (node (ref "U6") (pin "1") (pinfunction "Q1_1") (pintype "unspecified"))
    )
    (net (code "9") (name "/B_1A") (class "Default")
      (node (ref "H5") (pin "4") (pinfunction "4_4") (pintype "unspecified"))
      (node (ref "P10") (pin "3") (pinfunction "3_3") (pintype "unspecified"))
      (node (ref "R31") (pin "1") (pinfunction "1_1") (pintype "unspecified"))
    )
    (net (code "10") (name "/B_1B") (class "Default")
      (node (ref "H5") (pin "3") (pinfunction "3_3") (pintype "unspecified"))
      (node (ref "P10") (pin "4") (pinfunction "4_4") (pintype "unspecified"))
      (node (ref "R32") (pin "1") (pinfunction "1_1") (pintype "unspecified"))
    )
    (net (code "11") (name "/B_2A") (class "Default")
      (node (ref "H5") (pin "5") (pinfunction "5_5") (pintype "unspecified"))
      (node (ref "P10") (pin "2") (pinfunction "2_2") (pintype "unspecified"))
      (node (ref "R30") (pin "1") (pinfunction "1_1") (pintype "unspecified"))
    )
    (net (code "12") (name "/B_2B") (class "Default")
      (node (ref "H5") (pin "6") (pinfunction "6_6") (pintype "unspecified"))
      (node (ref "P10") (pin "1") (pinfunction "1_1") (pintype "unspecified"))
      (node (ref "R27") (pin "1") (pinfunction "1_1") (pintype "unspecified"))
    )
    (net (code "13") (name "/B_DIR_O") (class "Default")
      (node (ref "H4") (pin "1") (pinfunction "1_1") (pintype "unspecified"))
      (node (ref "U6") (pin "4") (pinfunction "Q4_4") (pintype "unspecified"))
    )
    (net (code "14") (name "/B_STEP_O") (class "Default")
      (node (ref "H4") (pin "2") (pinfunction "2_2") (pintype "unspecified"))
      (node (ref "U6") (pin "3") (pinfunction "Q3_3") (pintype "unspecified"))
    )
    (net (code "15") (name "/C_1A") (class "Default")
      (node (ref "H8") (pin "4") (pinfunction "4_4") (pintype "unspecified"))
      (node (ref "P14") (pin "3") (pinfunction "3_3") (pintype "unspecified"))
      (node (ref "R38") (pin "1") (pinfunction "1_1") (pintype "unspecified"))
    )
    (net (code "16") (name "/C_1B") (class "Default")
      (node (ref "H8") (pin "3") (pinfunction "3_3") (pintype "unspecified"))
      (node (ref "P14") (pin "4") (pinfunction "4_4") (pintype "unspecified"))
      (node (ref "R39") (pin "1") (pinfunction "1_1") (pintype "unspecified"))
    )
    (net (code "17") (name "/C_2A") (class "Default")
      (node (ref "H8") (pin "5") (pinfunction "5_5") (pintype "unspecified"))
      (node (ref "P14") (pin "2") (pinfunction "2_2") (pintype "unspecified"))
      (node (ref "R37") (pin "1") (pinfunction "1_1") (pintype "unspecified"))
    )
    (net (code "18") (name "/C_2B") (class "Default")
      (node (ref "H8") (pin "6") (pinfunction "6_6") (pintype "unspecified"))
      (node (ref "P14") (pin "1") (pinfunction "1_1") (pintype "unspecified"))
      (node (ref "R36") (pin "1") (pinfunction "1_1") (pintype "unspecified"))
    )
    (net (code "19") (name "/C_DIR_O") (class "Default")
      (node (ref "H7") (pin "1") (pinfunction "1_1") (pintype "unspecified"))
      (node (ref "U6") (pin "6") (pinfunction "Q6_6") (pintype "unspecified"))
    )
    (net (code "20") (name "/C_STEP_O") (class "Default")
      (node (ref "H7") (pin "2") (pinfunction "2_2") (pintype "unspecified"))
      (node (ref "U6") (pin "5") (pinfunction "Q5_5") (pintype "unspecified"))
    )
    (net (code "21") (name "/ESP_BOOT") (class "Default")
      (node (ref "K2") (pin "2") (pinfunction "2_2") (pintype "unspecified"))
      (node (ref "Q1") (pin "3") (pinfunction "C_3") (pintype "unspecified"))
      (node (ref "U9") (pin "25") (pinfunction "IO0_25") (pintype "unspecified"))
    )
    (net (code "22") (name "/ESP_RST") (class "Default")
      (node (ref "C23") (pin "2") (pinfunction "2_2") (pintype "unspecified"))
      (node (ref "Q2") (pin "3") (pinfunction "C_3") (pintype "unspecified"))
      (node (ref "R28") (pin "1") (pinfunction "1_1") (pintype "input"))
      (node (ref "R35") (pin "2") (pinfunction "2_2") (pintype "unspecified"))
      (node (ref "U9") (pin "3") (pinfunction "EN_3") (pintype "unspecified"))
    )
    (net (code "23") (name "/I2SO(0)") (class "Default")
      (node (ref "H1") (pin "1") (pinfunction "1_1") (pintype "unspecified"))
      (node (ref "U6") (pin "15") (pinfunction "Q0_15") (pintype "unspecified"))
    )
    (net (code "24") (name "/I2SO(8)") (class "Default")
      (node (ref "H9") (pin "4") (pinfunction "4_4") (pintype "unspecified"))
      (node (ref "U8") (pin "15") (pinfunction "Q0_15") (pintype "unspecified"))
    )
    (net (code "25") (name "/I2S_BCK") (class "Default")
      (node (ref "R16") (pin "1") (pinfunction "1_1") (pintype "unspecified"))
      (node (ref "U6") (pin "11") (pinfunction "SHCP_11") (pintype "unspecified"))
      (node (ref "U8") (pin "11") (pinfunction "SHCP_11") (pintype "unspecified"))
      (node (ref "U9") (pin "12") (pinfunction "IO27_12") (pintype "unspecified"))
    )
    (net (code "26") (name "/I2S_DATA") (class "Default")
      (node (ref "U6") (pin "14") (pinfunction "DS_14") (pintype "unspecified"))
      (node (ref "U9") (pin "10") (pinfunction "IO25_10") (pintype "unspecified"))
    )
    (net (code "27") (name "/I2S_WS") (class "Default")
      (node (ref "U6") (pin "12") (pinfunction "STCP_12") (pintype "unspecified"))
      (node (ref "U8") (pin "12") (pinfunction "STCP_12") (pintype "unspecified"))
      (node (ref "U9") (pin "11") (pinfunction "IO26_11") (pintype "unspecified"))
    )
    (net (code "28") (name "/IO2") (class "Default")
      (node (ref "U7") (pin "2") (pinfunction "A_2") (pintype "unspecified"))
      (node (ref "U9") (pin "24") (pinfunction "IO2_24") (pintype "unspecified"))
    )
    (net (code "29") (name "/IO2_OUT") (class "Default")
      (node (ref "P11") (pin "2") (pintype "input"))
      (node (ref "U7") (pin "4") (pinfunction "Y_4") (pintype "unspecified"))
    )
    (net (code "30") (name "/IO4") (class "Default")
      (node (ref "R21") (pin "1") (pinfunction "1_1") (pintype "input"))
      (node (ref "U9") (pin "26") (pinfunction "IO4_26") (pintype "unspecified"))
    )
    (net (code "31") (name "/IO4_OUT") (class "Default")
      (node (ref "D8") (pin "2") (pinfunction "2_2") (pintype "input"))
      (node (ref "P9") (pin "2") (pinfunction "2_2") (pintype "unspecified"))
      (node (ref "R17") (pin "2") (pinfunction "2_2") (pintype "unspecified"))
      (node (ref "R21") (pin "2") (pinfunction "2_2") (pintype "input"))
      (node (ref "R23") (pin "1") (pinfunction "1_1") (pintype "unspecified"))
    )
    (net (code "32") (name "/IO12") (class "Default")
      (node (ref "R47") (pin "1") (pinfunction "1_1") (pintype "input"))
      (node (ref "U12") (pin "2") (pinfunction "A_2") (pintype "unspecified"))
      (node (ref "U9") (pin "14") (pinfunction "IO12_14") (pintype "unspecified"))
    )
    (net (code "33") (name "/IO14") (class "Default")
      (node (ref "R42") (pin "1") (pinfunction "1_1") (pintype "input"))
      (node (ref "U9") (pin "13") (pinfunction "IO14_13") (pintype "unspecified"))
    )
    (net (code "34") (name "/IO14_IN") (class "Default")
      (node (ref "P17") (pin "1") (pintype "input"))
      (node (ref "R40") (pin "2") (pinfunction "2_2") (pintype "unspecified"))
      (node (ref "R42") (pin "2") (pinfunction "2_2") (pintype "input"))
      (node (ref "R44") (pin "1") (pinfunction "1_1") (pintype "unspecified"))
    )
    (net (code "35") (name "/IO15") (class "Default")
      (node (ref "R15") (pin "2") (pinfunction "2_2") (pintype "unspecified"))
      (node (ref "U5") (pin "4") (pinfunction "4_4") (pintype "unspecified"))
      (node (ref "U9") (pin "23") (pinfunction "IO15_23") (pintype "unspecified"))
    )
    (net (code "36") (name "/IO22") (class "Default")
      (node (ref "R13") (pin "1") (pinfunction "1_1") (pintype "input"))
      (node (ref "U4") (pin "2") (pinfunction "A_2") (pintype "unspecified"))
      (node (ref "U9") (pin "36") (pinfunction "IO22_36") (pintype "unspecified"))
    )
    (net (code "37") (name "/IO32") (class "Default")
      (node (ref "R29") (pin "1") (pinfunction "1_1") (pintype "input"))
      (node (ref "U9") (pin "8") (pinfunction "IO32_8") (pintype "unspecified"))
    )
    (net (code "38") (name "/IO32_IN") (class "Default")
      (node (ref "C19") (pin "2") (pinfunction "2_2") (pintype "unspecified"))
      (node (ref "D9") (pin "2") (pinfunction "2_2") (pintype "input"))
      (node (ref "P12") (pin "1") (pintype "input"))
      (node (ref "R26") (pin "2") (pinfunction "2_2") (pintype "unspecified"))
      (node (ref "R29") (pin "2") (pinfunction "2_2") (pintype "input"))
    )
    (net (code "39") (name "/IO33") (class "Default")
      (node (ref "R43") (pin "1") (pinfunction "1_1") (pintype "input"))
      (node (ref "U9") (pin "9") (pinfunction "IO33_9") (pintype "unspecified"))
    )
    (net (code "40") (name "/IO33_IN") (class "Default")
      (node (ref "D13") (pin "2") (pinfunction "2_2") (pintype "input"))
      (node (ref "P18") (pin "1") (pintype "input"))
      (node (ref "R41") (pin "2") (pinfunction "2_2") (pintype "unspecified"))
      (node (ref "R43") (pin "2") (pinfunction "2_2") (pintype "input"))
      (node (ref "R45") (pin "1") (pinfunction "1_1") (pintype "unspecified"))
    )
    (net (code "41") (name "/M_EN_O") (class "Default")
      (node (ref "P2") (pin "2") (pinfunction "2_2") (pintype "unspecified"))
      (node (ref "P2") (pin "4") (pinfunction "4_4") (pintype "unspecified"))
      (node (ref "P2") (pin "6") (pinfunction "6_6") (pintype "unspecified"))
      (node (ref "U8") (pin "1") (pinfunction "Q1_1") (pintype "unspecified"))
    )
    (net (code "42") (name "/PROBE") (class "Default")
      (node (ref "R34") (pin "2") (pinfunction "2_2") (pintype "unspecified"))
      (node (ref "U10") (pin "4") (pinfunction "4_4") (pintype "unspecified"))
      (node (ref "U9") (pin "7") (pinfunction "IO35_7") (pintype "unspecified"))
    )
    (net (code "43") (name "/PROBE_O") (class "Default")
      (node (ref "D10") (pin "2") (pinfunction "2_2") (pintype "input"))
      (node (ref "P13") (pin "2") (pinfunction "2_2") (pintype "unspecified"))
      (node (ref "U10") (pin "2") (pinfunction "2_2") (pintype "unspecified"))
    )
    (net (code "44") (name "/PWM") (class "Default")
      (node (ref "R50") (pin "1") (pinfunction "1_1") (pintype "input"))
      (node (ref "U13") (pin "2") (pinfunction "A_2") (pintype "unspecified"))
      (node (ref "U14") (pin "2") (pinfunction "A_2") (pintype "unspecified"))
      (node (ref "U9") (pin "16") (pinfunction "IO13_16") (pintype "unspecified"))
    )
    (net (code "45") (name "/PWM_5V") (class "Default")
      (node (ref "P20") (pin "1") (pinfunction "1_1") (pintype "unspecified"))
      (node (ref "U14") (pin "4") (pinfunction "Y_4") (pintype "unspecified"))
    )
    (net (code "46") (name "/PWM_LAS") (class "Default")
      (node (ref "P21") (pin "2") (pinfunction "2_2") (pintype "unspecified"))
      (node (ref "U13") (pin "4") (pinfunction "Y_4") (pintype "unspecified"))
    )
    (net (code "49") (name "/R1IN") (class "Default")
      (node (ref "P15") (pin "2") (pinfunction "2_2") (pintype "unspecified"))
      (node (ref "U11") (pin "13") (pinfunction "R1IN_13") (pintype "unspecified"))
    )
    (net (code "50") (name "/R1OUT") (class "Default")
      (node (ref "D11") (pin "1") (pinfunction "K_1") (pintype "input"))
      (node (ref "U11") (pin "12") (pinfunction "R1OUT_12") (pintype "unspecified"))
    )
    (net (code "51") (name "/R2IN") (class "Default")
      (node (ref "P16") (pin "2") (pinfunction "2_2") (pintype "unspecified"))
      (node (ref "U11") (pin "8") (pinfunction "R2IN_8") (pintype "unspecified"))
    )
    (net (code "52") (name "/R2OUT") (class "Default")
      (node (ref "R48") (pin "1") (pinfunction "1_1") (pintype "unspecified"))
      (node (ref "U11") (pin "9") (pinfunction "R2OUT_9") (pintype "unspecified"))
    )
    (net (code "53") (name "/RGB_OUT") (class "Default")
      (node (ref "D6") (pin "2") (pinfunction "2_2") (pintype "input"))
      (node (ref "P6") (pin "2") (pinfunction "2_2") (pintype "unspecified"))
      (node (ref "U4") (pin "4") (pinfunction "Y_4") (pintype "unspecified"))
    )
    (net (code "54") (name "/RX2") (class "Default")
      (node (ref "P22") (pin "2") (pinfunction "2_2") (pintype "unspecified"))
      (node (ref "R58") (pin "2") (pinfunction "2_2") (pintype "unspecified"))
    )
    (net (code "55") (name "/RXD") (class "Default")
      (node (ref "D11") (pin "2") (pinfunction "A_2") (pintype "input"))
      (node (ref "D14") (pin "1") (pinfunction "1_1") (pintype "unspecified"))
      (node (ref "D17") (pin "2") (pinfunction "A_2") (pintype "input"))
      (node (ref "H6") (pin "2") (pinfunction "2_2") (pintype "unspecified"))
      (node (ref "R51") (pin "1") (pinfunction "1_1") (pintype "unspecified"))
      (node (ref "U9") (pin "34") (pinfunction "RXD0_34") (pintype "unspecified"))
    )
    (net (code "56") (name "/RXD2") (class "Default")
      (node (ref "H9") (pin "1") (pinfunction "1_1") (pintype "unspecified"))
      (node (ref "R48") (pin "2") (pinfunction "2_2") (pintype "unspecified"))
      (node (ref "R58") (pin "1") (pinfunction "1_1") (pintype "unspecified"))
      (node (ref "U9") (pin "27") (pinfunction "IO16_27") (pintype "unspecified"))
    )
    (net (code "57") (name "/SD_CD") (class "Default")
      (node (ref "R60") (pin "1") (pinfunction "1_1") (pintype "unspecified"))
      (node (ref "U16") (pin "9") (pinfunction "CD_9") (pintype "unspecified"))
      (node (ref "U9") (pin "33") (pinfunction "IO21_33") (pintype "unspecified"))
    )
    (net (code "58") (name "/SD_CS") (class "Default")
      (node (ref "R54") (pin "1") (pinfunction "1_1") (pintype "unspecified"))
      (node (ref "U16") (pin "2") (pinfunction "CD/DAT3_2") (pintype "unspecified"))
      (node (ref "U9") (pin "29") (pinfunction "IO5_29") (pintype "unspecified"))
    )
    (net (code "59") (name "/SD_MISO") (class "Default")
      (node (ref "R57") (pin "1") (pinfunction "1_1") (pintype "unspecified"))
      (node (ref "U16") (pin "7") (pinfunction "DAT0_7") (pintype "unspecified"))
      (node (ref "U9") (pin "31") (pinfunction "IO19_31") (pintype "unspecified"))
    )
    (net (code "60") (name "/SD_MOSI") (class "Default")
      (node (ref "R55") (pin "1") (pinfunction "1_1") (pintype "unspecified"))
      (node (ref "U16") (pin "3") (pinfunction "CMD_3") (pintype "unspecified"))
      (node (ref "U9") (pin "37") (pinfunction "IO23_37") (pintype "unspecified"))
    )
    (net (code "61") (name "/SD_SCLK") (class "Default")
      (node (ref "U16") (pin "5") (pinfunction "CLX_5") (pintype "unspecified"))
      (node (ref "U9") (pin "30") (pinfunction "IO18_30") (pintype "unspecified"))
    )
    (net (code "62") (name "/SW3_OUT") (class "Default")
      (node (ref "P19") (pin "3") (pinfunction "3_3") (pintype "unspecified"))
      (node (ref "U12") (pin "4") (pinfunction "Y_4") (pintype "unspecified"))
    )
    (net (code "63") (name "/T1IN") (class "Default")
      (node (ref "D12") (pin "2") (pinfunction "A_2") (pintype "input"))
      (node (ref "R49") (pin "2") (pinfunction "2_2") (pintype "unspecified"))
      (node (ref "U11") (pin "11") (pinfunction "T1IN_11") (pintype "unspecified"))
    )
    (net (code "64") (name "/T1OUT") (class "Default")
      (node (ref "P15") (pin "3") (pinfunction "3_3") (pintype "unspecified"))
      (node (ref "U11") (pin "14") (pinfunction "T1OUT_14") (pintype "unspecified"))
    )
    (net (code "65") (name "/T2IN") (class "Default")
      (node (ref "R46") (pin "1") (pinfunction "1_1") (pintype "unspecified"))
      (node (ref "U11") (pin "10") (pinfunction "T2IN_10") (pintype "unspecified"))
    )
    (net (code "66") (name "/T2OUT") (class "Default")
      (node (ref "P16") (pin "3") (pinfunction "3_3") (pintype "unspecified"))
      (node (ref "U11") (pin "7") (pinfunction "T2OUT_7") (pintype "unspecified"))
    )
    (net (code "67") (name "/TX2") (class "Default")
      (node (ref "P22") (pin "3") (pinfunction "3_3") (pintype "unspecified"))
      (node (ref "R56") (pin "2") (pinfunction "2_2") (pintype "unspecified"))
    )
    (net (code "68") (name "/TXD") (class "Default")
      (node (ref "D12") (pin "1") (pinfunction "K_1") (pintype "input"))
      (node (ref "D16") (pin "1") (pinfunction "K_1") (pintype "input"))
      (node (ref "H6") (pin "1") (pinfunction "1_1") (pintype "unspecified"))
      (node (ref "U9") (pin "35") (pinfunction "TXD0_35") (pintype "unspecified"))
    )
    (net (code "69") (name "/TXD2") (class "Default")
      (node (ref "H9") (pin "2") (pinfunction "2_2") (pintype "unspecified"))
      (node (ref "R46") (pin "2") (pinfunction "2_2") (pintype "unspecified"))
      (node (ref "R56") (pin "1") (pinfunction "1_1") (pintype "unspecified"))
      (node (ref "U9") (pin "28") (pinfunction "IO17_28") (pintype "unspecified"))
    )
    (net (code "70") (name "/USB_DM") (class "Default")
      (node (ref "P23") (pin "2") (pinfunction "D-_2") (pintype "unspecified"))
      (node (ref "U17") (pin "3") (pinfunction "3_3") (pintype "unspecified"))
    )
    (net (code "71") (name "/USB_DP") (class "Default")
      (node (ref "P23") (pin "3") (pinfunction "D+_3") (pintype "unspecified"))
      (node (ref "U17") (pin "1") (pinfunction "1_1") (pintype "unspecified"))
    )
    (net (code "72") (name "/X_DIR_O") (class "Default")
      (node (ref "P2") (pin "10") (pinfunction "10_10") (pintype "unspecified"))
      (node (ref "U8") (pin "3") (pinfunction "Q3_3") (pintype "unspecified"))
    )
    (net (code "73") (name "/X_LIMT") (class "Default")
      (node (ref "R2") (pin "2") (pinfunction "2_2") (pintype "unspecified"))
      (node (ref "U9") (pin "6") (pinfunction "IO34_6") (pintype "unspecified"))
    )
    (net (code "74") (name "/X_LIMT_I") (class "Default")
      (node (ref "P1") (pin "2") (pinfunction "2_2") (pintype "unspecified"))
      (node (ref "P1") (pin "4") (pinfunction "4_4") (pintype "unspecified"))
      (node (ref "R1") (pin "1") (pinfunction "1_1") (pintype "unspecified"))
      (node (ref "R2") (pin "1") (pinfunction "1_1") (pintype "unspecified"))
      (node (ref "R3") (pin "1") (pinfunction "1_1") (pintype "unspecified"))
    )
    (net (code "75") (name "/X_STEP_O") (class "Default")
      (node (ref "P2") (pin "8") (pinfunction "8_8") (pintype "unspecified"))
      (node (ref "U8") (pin "2") (pinfunction "Q2_2") (pintype "unspecified"))
    )
    (net (code "76") (name "/Y_DIR_O") (class "Default")
      (node (ref "P2") (pin "14") (pinfunction "14_14") (pintype "unspecified"))
      (node (ref "U8") (pin "5") (pinfunction "Q5_5") (pintype "unspecified"))
    )
    (net (code "77") (name "/Y_LIMT") (class "Default")
      (node (ref "R6") (pin "2") (pinfunction "2_2") (pintype "unspecified"))
      (node (ref "U9") (pin "5") (pinfunction "SENSOR_VN_5") (pintype "unspecified"))
    )
    (net (code "78") (name "/Y_LIMT_I") (class "Default")
      (node (ref "P1") (pin "6") (pinfunction "6_6") (pintype "unspecified"))
      (node (ref "P1") (pin "8") (pinfunction "8_8") (pintype "unspecified"))
      (node (ref "R5") (pin "1") (pinfunction "1_1") (pintype "unspecified"))
      (node (ref "R6") (pin "1") (pinfunction "1_1") (pintype "unspecified"))
      (node (ref "R7") (pin "1") (pinfunction "1_1") (pintype "unspecified"))
    )
    (net (code "79") (name "/Y_STEP_O") (class "Default")
      (node (ref "P2") (pin "12") (pinfunction "12_12") (pintype "unspecified"))
      (node (ref "U8") (pin "4") (pinfunction "Q4_4") (pintype "unspecified"))
    )
    (net (code "80") (name "/Z_DIR_O") (class "Default")
      (node (ref "P2") (pin "18") (pinfunction "18_18") (pintype "unspecified"))
      (node (ref "U8") (pin "7") (pinfunction "Q7_7") (pintype "unspecified"))
    )
    (net (code "81") (name "/Z_LIMT") (class "Default")
      (node (ref "R11") (pin "2") (pinfunction "2_2") (pintype "unspecified"))
      (node (ref "U9") (pin "4") (pinfunction "SENSOR_VP_4") (pintype "unspecified"))
    )
    (net (code "82") (name "/Z_LIMT_I") (class "Default")
      (node (ref "P1") (pin "10") (pinfunction "10_10") (pintype "unspecified"))
      (node (ref "P1") (pin "12") (pinfunction "12_12") (pintype "unspecified"))
      (node (ref "R10") (pin "1") (pinfunction "1_1") (pintype "unspecified"))
      (node (ref "R11") (pin "1") (pinfunction "1_1") (pintype "unspecified"))
      (node (ref "R12") (pin "1") (pinfunction "1_1") (pintype "unspecified"))
    )
    (net (code "83") (name "/Z_STEP_O") (class "Default")
      (node (ref "P2") (pin "16") (pinfunction "16_16") (pintype "unspecified"))
      (node (ref "U8") (pin "6") (pinfunction "Q6_6") (pintype "unspecified"))
    )
    (net (code "84") (name "3V3") (class "Default")
      (node (ref "C10") (pin "2") (pinfunction "2_2") (pintype "unspecified"))
      (node (ref "C21") (pin "1") (pinfunction "1_1") (pintype "unspecified"))
      (node (ref "C38") (pin "2") (pinfunction "2_2") (pintype "unspecified"))
      (node (ref "C8") (pin "2") (pinfunction "2_2") (pintype "input"))
      (node (ref "C9") (pin "2") (pinfunction "2_2") (pintype "input"))
      (node (ref "R25") (pin "1") (pinfunction "1_1") (pintype "unspecified"))
      (node (ref "R35") (pin "1") (pinfunction "1_1") (pintype "unspecified"))
      (node (ref "R51") (pin "2") (pinfunction "2_2") (pintype "unspecified"))
      (node (ref "R54") (pin "2") (pinfunction "2_2") (pintype "unspecified"))
      (node (ref "R55") (pin "2") (pinfunction "2_2") (pintype "unspecified"))
      (node (ref "R57") (pin "2") (pinfunction "2_2") (pintype "unspecified"))
      (node (ref "R60") (pin "2") (pinfunction "2_2") (pintype "unspecified"))
      (node (ref "U16") (pin "4") (pinfunction "VDD_4") (pintype "unspecified"))
      (node (ref "U3") (pin "2") (pinfunction "OUT_2") (pintype "unspecified"))
      (node (ref "U3") (pin "4") (pinfunction "=_4") (pintype "unspecified"))
      (node (ref "U9") (pin "2") (pinfunction "3V3_2") (pintype "unspecified"))
    )
    (net (code "86") (name "5V_VCC") (class "Default")
      (node (ref "C12") (pin "1") (pinfunction "1_1") (pintype "unspecified"))
      (node (ref "C15") (pin "1") (pinfunction "1_1") (pintype "unspecified"))
      (node (ref "C16") (pin "2") (pinfunction "2_2") (pintype "unspecified"))
      (node (ref "C26") (pin "2") (pinfunction "2_2") (pintype "unspecified"))
      (node (ref "C29") (pin "2") (pinfunction "2_2") (pintype "unspecified"))
      (node (ref "C32") (pin "2") (pinfunction "2_2") (pintype "unspecified"))
      (node (ref "C33") (pin "1") (pinfunction "1_1") (pintype "unspecified"))
      (node (ref "C34") (pin "1") (pinfunction "1_1") (pintype "input"))
      (node (ref "C6") (pin "1") (pinfunction "1_1") (pintype "input"))
      (node (ref "C7") (pin "1") (pinfunction "1_1") (pintype "input"))
      (node (ref "D15") (pin "1") (pinfunction "K_1") (pintype "input"))
      (node (ref "D4") (pin "2") (pinfunction "2_2") (pintype "input"))
      (node (ref "H2") (pin "5") (pinfunction "5_5") (pintype "unspecified"))
      (node (ref "H2") (pin "6") (pinfunction "6_6") (pintype "unspecified"))
      (node (ref "H2") (pin "7") (pinfunction "7_7") (pintype "unspecified"))
      (node (ref "H3") (pin "2") (pinfunction "2_2") (pintype "unspecified"))
      (node (ref "H4") (pin "5") (pinfunction "5_5") (pintype "unspecified"))
      (node (ref "H4") (pin "6") (pinfunction "6_6") (pintype "unspecified"))
      (node (ref "H4") (pin "7") (pinfunction "7_7") (pintype "unspecified"))
      (node (ref "H5") (pin "2") (pinfunction "2_2") (pintype "unspecified"))
      (node (ref "H7") (pin "5") (pinfunction "5_5") (pintype "unspecified"))
      (node (ref "H7") (pin "6") (pinfunction "6_6") (pintype "unspecified"))
      (node (ref "H7") (pin "7") (pinfunction "7_7") (pintype "unspecified"))
      (node (ref "H8") (pin "2") (pinfunction "2_2") (pintype "unspecified"))
      (node (ref "L1") (pin "1") (pinfunction "1_1") (pintype "unspecified"))
      (node (ref "P13") (pin "3") (pinfunction "3_3") (pintype "unspecified"))
      (node (ref "P2") (pin "1") (pinfunction "1_1") (pintype "unspecified"))
      (node (ref "P2") (pin "11") (pinfunction "11_11") (pintype "unspecified"))
      (node (ref "P2") (pin "13") (pinfunction "13_13") (pintype "unspecified"))
      (node (ref "P2") (pin "15") (pinfunction "15_15") (pintype "unspecified"))
      (node (ref "P2") (pin "17") (pinfunction "17_17") (pintype "unspecified"))
      (node (ref "P2") (pin "3") (pinfunction "3_3") (pintype "unspecified"))
      (node (ref "P2") (pin "5") (pinfunction "5_5") (pintype "unspecified"))
      (node (ref "P2") (pin "7") (pinfunction "7_7") (pintype "unspecified"))
      (node (ref "P2") (pin "9") (pinfunction "9_9") (pintype "unspecified"))
      (node (ref "P22") (pin "1") (pinfunction "1_1") (pintype "unspecified"))
      (node (ref "P6") (pin "3") (pinfunction "3_3") (pintype "unspecified"))
      (node (ref "P9") (pin "3") (pinfunction "3_3") (pintype "unspecified"))
      (node (ref "R1") (pin "2") (pinfunction "2_2") (pintype "unspecified"))
      (node (ref "R10") (pin "2") (pinfunction "2_2") (pintype "unspecified"))
      (node (ref "R15") (pin "1") (pinfunction "1_1") (pintype "unspecified"))
      (node (ref "R17") (pin "1") (pinfunction "1_1") (pintype "unspecified"))
      (node (ref "R24") (pin "2") (pinfunction "2_2") (pintype "input"))
      (node (ref "R26") (pin "1") (pinfunction "1_1") (pintype "unspecified"))
      (node (ref "R33") (pin "1") (pinfunction "1_1") (pintype "unspecified"))
      (node (ref "R34") (pin "1") (pinfunction "1_1") (pintype "unspecified"))
      (node (ref "R40") (pin "1") (pinfunction "1_1") (pintype "unspecified"))
      (node (ref "R41") (pin "1") (pinfunction "1_1") (pintype "unspecified"))
      (node (ref "R49") (pin "1") (pinfunction "1_1") (pintype "unspecified"))
      (node (ref "R5") (pin "2") (pinfunction "2_2") (pintype "unspecified"))
      (node (ref "R52") (pin "1") (pinfunction "1_1") (pintype "unspecified"))
      (node (ref "R8") (pin "2") (pinfunction "2_2") (pintype "unspecified"))
      (node (ref "U11") (pin "16") (pinfunction "VCC_16") (pintype "unspecified"))
      (node (ref "U12") (pin "5") (pinfunction "VCC_5") (pintype "unspecified"))
      (node (ref "U13") (pin "5") (pinfunction "VCC_5") (pintype "unspecified"))
      (node (ref "U14") (pin "5") (pinfunction "VCC_5") (pintype "unspecified"))
      (node (ref "U15") (pin "16") (pinfunction "VCC_16") (pintype "unspecified"))
      (node (ref "U2") (pin "3") (pinfunction "FB_3") (pintype "input"))
      (node (ref "U3") (pin "3") (pinfunction "IN_3") (pintype "unspecified"))
      (node (ref "U4") (pin "5") (pinfunction "VCC_5") (pintype "unspecified"))
      (node (ref "U6") (pin "16") (pinfunction "VCC_16") (pintype "unspecified"))
      (node (ref "U7") (pin "5") (pinfunction "VCC_5") (pintype "unspecified"))
      (node (ref "U8") (pin "16") (pinfunction "VCC_16") (pintype "unspecified"))
    )
    (net (code "87") (name "12V") (class "Default")
      (node (ref "C1") (pin "1") (pintype "unspecified"))
      (node (ref "C13") (pin "1") (pintype "unspecified"))
      (node (ref "D1") (pin "1") (pinfunction "1_1") (pintype "unspecified"))
      (node (ref "H3") (pin "8") (pinfunction "8_8") (pintype "unspecified"))
      (node (ref "P15") (pin "1") (pinfunction "1_1") (pintype "unspecified"))
      (node (ref "P16") (pin "1") (pinfunction "1_1") (pintype "unspecified"))
      (node (ref "P2") (pin "22") (pinfunction "22_22") (pintype "unspecified"))
      (node (ref "P2") (pin "23") (pinfunction "23_23") (pintype "unspecified"))
      (node (ref "P2") (pin "24") (pinfunction "24_24") (pintype "unspecified"))
      (node (ref "P21") (pin "1") (pinfunction "1_1") (pintype "unspecified"))
      (node (ref "P3") (pin "2") (pintype "input"))
      (node (ref "P4") (pin "2") (pintype "input"))
      (node (ref "P5") (pin "1") (pinfunction "1_1") (pintype "unspecified"))
      (node (ref "P7") (pin "1") (pinfunction "1_1") (pintype "unspecified"))
      (node (ref "R14") (pin "1") (pinfunction "1_1") (pintype "unspecified"))
      (node (ref "R4") (pin "2") (pinfunction "2_2") (pintype "unspecified"))
      (node (ref "U1") (pin "1") (pinfunction "IN_1") (pintype "unspecified"))
    )
    (net (code "88") (name "12V_DIV") (class "Default")
      (node (ref "C18") (pin "1") (pintype "unspecified"))
      (node (ref "C22") (pin "1") (pintype "unspecified"))
      (node (ref "H5") (pin "8") (pinfunction "8_8") (pintype "unspecified"))
      (node (ref "H8") (pin "8") (pinfunction "8_8") (pintype "unspecified"))
      (node (ref "U1") (pin "3") (pinfunction "OUT_3") (pintype "unspecified"))
    )
    (net (code "90") (name "GND") (class "Default")
      (node (ref "C1") (pin "2") (pintype "unspecified"))
      (node (ref "C10") (pin "1") (pinfunction "1_1") (pintype "unspecified"))
      (node (ref "C11") (pin "2") (pinfunction "2_2") (pintype "unspecified"))
      (node (ref "C12") (pin "2") (pinfunction "2_2") (pintype "unspecified"))
      (node (ref "C13") (pin "2") (pintype "unspecified"))
      (node (ref "C14") (pin "1") (pinfunction "1_1") (pintype "unspecified"))
      (node (ref "C15") (pin "2") (pinfunction "2_2") (pintype "unspecified"))
      (node (ref "C16") (pin "1") (pinfunction "1_1") (pintype "unspecified"))
      (node (ref "C17") (pin "1") (pinfunction "1_1") (pintype "unspecified"))
      (node (ref "C18") (pin "2") (pintype "unspecified"))
      (node (ref "C19") (pin "1") (pinfunction "1_1") (pintype "unspecified"))
      (node (ref "C2") (pin "2") (pintype "unspecified"))
      (node (ref "C20") (pin "1") (pinfunction "1_1") (pintype "unspecified"))
      (node (ref "C21") (pin "2") (pinfunction "2_2") (pintype "unspecified"))
      (node (ref "C22") (pin "2") (pintype "unspecified"))
      (node (ref "C23") (pin "1") (pinfunction "1_1") (pintype "unspecified"))
      (node (ref "C24") (pin "1") (pinfunction "1_1") (pintype "unspecified"))
      (node (ref "C26") (pin "1") (pinfunction "1_1") (pintype "unspecified"))
      (node (ref "C28") (pin "2") (pinfunction "2_2") (pintype "unspecified"))
      (node (ref "C29") (pin "1") (pinfunction "1_1") (pintype "unspecified"))
      (node (ref "C3") (pin "2") (pinfunction "2_2") (pintype "unspecified"))
      (node (ref "C30") (pin "1") (pinfunction "1_1") (pintype "unspecified"))
      (node (ref "C31") (pin "1") (pinfunction "1_1") (pintype "unspecified"))
      (node (ref "C32") (pin "1") (pinfunction "1_1") (pintype "unspecified"))
      (node (ref "C33") (pin "2") (pinfunction "2_2") (pintype "unspecified"))
      (node (ref "C34") (pin "2") (pinfunction "2_2") (pintype "input"))
      (node (ref "C35") (pin "2") (pinfunction "2_2") (pintype "unspecified"))
      (node (ref "C36") (pin "2") (pinfunction "2_2") (pintype "unspecified"))
      (node (ref "C37") (pin "2") (pinfunction "2_2") (pintype "unspecified"))
      (node (ref "C38") (pin "1") (pinfunction "1_1") (pintype "unspecified"))
      (node (ref "C4") (pin "1") (pinfunction "1_1") (pintype "unspecified"))
      (node (ref "C5") (pin "2") (pinfunction "2_2") (pintype "unspecified"))
      (node (ref "C6") (pin "2") (pinfunction "2_2") (pintype "input"))
      (node (ref "C7") (pin "2") (pinfunction "2_2") (pintype "input"))
      (node (ref "C8") (pin "1") (pinfunction "1_1") (pintype "input"))
      (node (ref "C9") (pin "1") (pinfunction "1_1") (pintype "input"))
      (node (ref "D10") (pin "1") (pinfunction "1_1") (pintype "input"))
      (node (ref "D13") (pin "1") (pinfunction "1_1") (pintype "input"))
      (node (ref "D14") (pin "2") (pinfunction "2_2") (pintype "unspecified"))
      (node (ref "D2") (pin "1") (pinfunction "1_1") (pintype "input"))
      (node (ref "D3") (pin "2") (pinfunction "2_2") (pintype "unspecified"))
      (node (ref "D4") (pin "1") (pinfunction "1_1") (pintype "input"))
      (node (ref "D5") (pin "2") (pinfunction "2_2") (pintype "unspecified"))
      (node (ref "D6") (pin "1") (pinfunction "1_1") (pintype "input"))
      (node (ref "D7") (pin "1") (pinfunction "1_1") (pintype "input"))
      (node (ref "D8") (pin "1") (pinfunction "1_1") (pintype "input"))
      (node (ref "D9") (pin "1") (pinfunction "1_1") (pintype "input"))
      (node (ref "H1") (pin "2") (pinfunction "2_2") (pintype "unspecified"))
      (node (ref "H3") (pin "1") (pinfunction "1_1") (pintype "unspecified"))
      (node (ref "H3") (pin "7") (pinfunction "7_7") (pintype "unspecified"))
      (node (ref "H5") (pin "1") (pinfunction "1_1") (pintype "unspecified"))
      (node (ref "H5") (pin "7") (pinfunction "7_7") (pintype "unspecified"))
      (node (ref "H8") (pin "1") (pinfunction "1_1") (pintype "unspecified"))
      (node (ref "H8") (pin "7") (pinfunction "7_7") (pintype "unspecified"))
      (node (ref "H9") (pin "3") (pinfunction "3_3") (pintype "unspecified"))
      (node (ref "K1") (pin "1") (pinfunction "1_1") (pintype "unspecified"))
      (node (ref "K1") (pin "2") (pinfunction "2_2") (pintype "unspecified"))
      (node (ref "K2") (pin "1") (pinfunction "1_1") (pintype "unspecified"))
      (node (ref "P1") (pin "1") (pinfunction "1_1") (pintype "unspecified"))
      (node (ref "P1") (pin "11") (pinfunction "11_11") (pintype "unspecified"))
      (node (ref "P1") (pin "3") (pinfunction "3_3") (pintype "unspecified"))
      (node (ref "P1") (pin "5") (pinfunction "5_5") (pintype "unspecified"))
      (node (ref "P1") (pin "7") (pinfunction "7_7") (pintype "unspecified"))
      (node (ref "P1") (pin "9") (pinfunction "9_9") (pintype "unspecified"))
      (node (ref "P11") (pin "1") (pintype "input"))
      (node (ref "P12") (pin "2") (pintype "input"))
      (node (ref "P13") (pin "1") (pinfunction "1_1") (pintype "unspecified"))
      (node (ref "P15") (pin "4") (pinfunction "4_4") (pintype "unspecified"))
      (node (ref "P16") (pin "4") (pinfunction "4_4") (pintype "unspecified"))
      (node (ref "P17") (pin "2") (pintype "input"))
      (node (ref "P18") (pin "2") (pintype "input"))
      (node (ref "P19") (pin "2") (pinfunction "2_2") (pintype "unspecified"))
      (node (ref "P2") (pin "19") (pinfunction "19_19") (pintype "unspecified"))
      (node (ref "P2") (pin "20") (pinfunction "20_20") (pintype "unspecified"))
      (node (ref "P2") (pin "21") (pinfunction "21_21") (pintype "unspecified"))
      (node (ref "P20") (pin "3") (pinfunction "3_3") (pintype "unspecified"))
      (node (ref "P21") (pin "3") (pinfunction "3_3") (pintype "unspecified"))
      (node (ref "P22") (pin "4") (pinfunction "4_4") (pintype "unspecified"))
      (node (ref "P23") (pin "4") (pinfunction "GND_4") (pintype "unspecified"))
      (node (ref "P23") (pin "5") (pinfunction "GND_5") (pintype "unspecified"))
      (node (ref "P23") (pin "6") (pinfunction "GND_6") (pintype "unspecified"))
      (node (ref "P3") (pin "1") (pintype "input"))
      (node (ref "P4") (pin "1") (pintype "input"))
      (node (ref "P5") (pin "2") (pinfunction "2_2") (pintype "unspecified"))
      (node (ref "P6") (pin "1") (pinfunction "1_1") (pintype "unspecified"))
      (node (ref "P7") (pin "3") (pinfunction "3_3") (pintype "unspecified"))
      (node (ref "P9") (pin "1") (pinfunction "1_1") (pintype "unspecified"))
      (node (ref "R13") (pin "2") (pinfunction "2_2") (pintype "input"))
      (node (ref "R16") (pin "2") (pinfunction "2_2") (pintype "unspecified"))
      (node (ref "R18") (pin "2") (pinfunction "2_2") (pintype "unspecified"))
      (node (ref "R19") (pin "2") (pinfunction "2_2") (pintype "unspecified"))
      (node (ref "R20") (pin "2") (pinfunction "2_2") (pintype "unspecified"))
      (node (ref "R22") (pin "2") (pinfunction "2_2") (pintype "unspecified"))
      (node (ref "R27") (pin "2") (pinfunction "2_2") (pintype "unspecified"))
      (node (ref "R30") (pin "2") (pinfunction "2_2") (pintype "unspecified"))
      (node (ref "R31") (pin "2") (pinfunction "2_2") (pintype "unspecified"))
      (node (ref "R32") (pin "2") (pinfunction "2_2") (pintype "unspecified"))
      (node (ref "R36") (pin "2") (pinfunction "2_2") (pintype "unspecified"))
      (node (ref "R37") (pin "2") (pinfunction "2_2") (pintype "unspecified"))
      (node (ref "R38") (pin "2") (pinfunction "2_2") (pintype "unspecified"))
      (node (ref "R39") (pin "2") (pinfunction "2_2") (pintype "unspecified"))
      (node (ref "R47") (pin "2") (pinfunction "2_2") (pintype "input"))
      (node (ref "R50") (pin "2") (pinfunction "2_2") (pintype "input"))
      (node (ref "R9") (pin "2") (pinfunction "2_2") (pintype "unspecified"))
      (node (ref "U1") (pin "2") (pinfunction "TAB_2") (pintype "unspecified"))
      (node (ref "U10") (pin "3") (pinfunction "3_3") (pintype "unspecified"))
      (node (ref "U11") (pin "15") (pinfunction "GND_15") (pintype "unspecified"))
      (node (ref "U12") (pin "3") (pinfunction "GND_3") (pintype "unspecified"))
      (node (ref "U13") (pin "3") (pinfunction "GND_3") (pintype "unspecified"))
      (node (ref "U14") (pin "3") (pinfunction "GND_3") (pintype "unspecified"))
      (node (ref "U15") (pin "1") (pinfunction "GND_1") (pintype "unspecified"))
      (node (ref "U16") (pin "10") (pinfunction "GND_10") (pintype "unspecified"))
      (node (ref "U16") (pin "11") (pinfunction "GND_11") (pintype "unspecified"))
      (node (ref "U16") (pin "12") (pinfunction "GND_12") (pintype "unspecified"))
      (node (ref "U16") (pin "13") (pinfunction "GND_13") (pintype "unspecified"))
      (node (ref "U16") (pin "6") (pinfunction "VSS_6") (pintype "unspecified"))
      (node (ref "U17") (pin "2") (pinfunction "2_2") (pintype "unspecified"))
      (node (ref "U2") (pin "5") (pinfunction "GND_5") (pintype "input"))
      (node (ref "U2") (pin "6") (pinfunction "GND_6") (pintype "input"))
      (node (ref "U2") (pin "7") (pinfunction "GND_7") (pintype "input"))
      (node (ref "U2") (pin "8") (pinfunction "GND_8") (pintype "input"))
      (node (ref "U3") (pin "1") (pinfunction "GND_1") (pintype "unspecified"))
      (node (ref "U4") (pin "3") (pinfunction "GND_3") (pintype "unspecified"))
      (node (ref "U5") (pin "3") (pinfunction "3_3") (pintype "unspecified"))
      (node (ref "U6") (pin "13") (pinfunction "OE#_13") (pintype "unspecified"))
      (node (ref "U6") (pin "8") (pinfunction "GND_8") (pintype "unspecified"))
      (node (ref "U7") (pin "3") (pinfunction "GND_3") (pintype "unspecified"))
      (node (ref "U8") (pin "13") (pinfunction "OE#_13") (pintype "unspecified"))
      (node (ref "U8") (pin "8") (pinfunction "GND_8") (pintype "unspecified"))
      (node (ref "U9") (pin "1") (pinfunction "GND_1") (pintype "unspecified"))
      (node (ref "U9") (pin "15") (pinfunction "GND_15") (pintype "unspecified"))
      (node (ref "U9") (pin "38") (pinfunction "GND_38") (pintype "unspecified"))
      (node (ref "U9") (pin "39") (pinfunction "EP_39") (pintype "unspecified"))
    )
    (net (code "91") (name "I2S_MR#") (class "Default")
      (node (ref "C17") (pin "2") (pinfunction "2_2") (pintype "unspecified"))
      (node (ref "R24") (pin "1") (pinfunction "1_1") (pintype "input"))
      (node (ref "U6") (pin "10") (pinfunction "MR#_10") (pintype "unspecified"))
      (node (ref "U8") (pin "10") (pinfunction "MR#_10") (pintype "unspecified"))
    )
    (net (code "92") (name "Net-(C3-Pad1)") (class "Default")
      (node (ref "C3") (pin "1") (pinfunction "1_1") (pintype "unspecified"))
      (node (ref "R3") (pin "2") (pinfunction "2_2") (pintype "unspecified"))
    )
    (net (code "93") (name "Net-(C5-Pad1)") (class "Default")
      (node (ref "C5") (pin "1") (pinfunction "1_1") (pintype "unspecified"))
      (node (ref "R7") (pin "2") (pinfunction "2_2") (pintype "unspecified"))
    )
    (net (code "94") (name "Net-(C11-Pad1)") (class "Default")
      (node (ref "C11") (pin "1") (pinfunction "1_1") (pintype "unspecified"))
      (node (ref "R12") (pin "2") (pinfunction "2_2") (pintype "unspecified"))
    )
    (net (code "95") (name "Net-(C14-Pad2)") (class "Default")
      (node (ref "C14") (pin "2") (pinfunction "2_2") (pintype "unspecified"))
      (node (ref "R23") (pin "2") (pinfunction "2_2") (pintype "unspecified"))
    )
    (net (code "96") (name "Net-(C20-Pad2)") (class "Default")
      (node (ref "C20") (pin "2") (pinfunction "2_2") (pintype "unspecified"))
      (node (ref "K1") (pin "3") (pinfunction "3_3") (pintype "unspecified"))
      (node (ref "K1") (pin "4") (pinfunction "4_4") (pintype "unspecified"))
      (node (ref "R25") (pin "2") (pinfunction "2_2") (pintype "unspecified"))
      (node (ref "R28") (pin "2") (pinfunction "2_2") (pintype "input"))
    )
    (net (code "97") (name "Net-(C30-Pad2)") (class "Default")
      (node (ref "C30") (pin "2") (pinfunction "2_2") (pintype "unspecified"))
      (node (ref "R44") (pin "2") (pinfunction "2_2") (pintype "unspecified"))
    )
    (net (code "98") (name "Net-(C31-Pad2)") (class "Default")
      (node (ref "C31") (pin "2") (pinfunction "2_2") (pintype "unspecified"))
      (node (ref "R45") (pin "2") (pinfunction "2_2") (pintype "unspecified"))
    )
    (net (code "99") (name "Net-(D3-Pad1)") (class "Default")
      (node (ref "D3") (pin "1") (pinfunction "1_1") (pintype "unspecified"))
      (node (ref "R4") (pin "1") (pinfunction "1_1") (pintype "unspecified"))
    )
    (net (code "100") (name "Net-(D5-Pad1)") (class "Default")
      (node (ref "D5") (pin "1") (pinfunction "1_1") (pintype "unspecified"))
      (node (ref "R8") (pin "1") (pinfunction "1_1") (pintype "unspecified"))
    )
    (net (code "101") (name "Net-(D16-A)") (class "Default")
      (node (ref "D16") (pin "2") (pinfunction "A_2") (pintype "input"))
      (node (ref "R52") (pin "2") (pinfunction "2_2") (pintype "unspecified"))
      (node (ref "U15") (pin "3") (pinfunction "RXD_3") (pintype "unspecified"))
    )
    (net (code "102") (name "Net-(D17-K)") (class "Default")
      (node (ref "D17") (pin "1") (pinfunction "K_1") (pintype "input"))
      (node (ref "U15") (pin "2") (pinfunction "TXD_2") (pintype "unspecified"))
    )
    (net (code "103") (name "Net-(H2-Pad3)") (class "Default")
      (node (ref "H2") (pin "3") (pinfunction "3_3") (pintype "unspecified"))
      (node (ref "H2") (pin "4") (pinfunction "4_4") (pintype "unspecified"))
    )
    (net (code "104") (name "Net-(H4-Pad3)") (class "Default")
      (node (ref "H4") (pin "3") (pinfunction "3_3") (pintype "unspecified"))
      (node (ref "H4") (pin "4") (pinfunction "4_4") (pintype "unspecified"))
    )
    (net (code "105") (name "Net-(H7-Pad3)") (class "Default")
      (node (ref "H7") (pin "3") (pinfunction "3_3") (pintype "unspecified"))
      (node (ref "H7") (pin "4") (pinfunction "4_4") (pintype "unspecified"))
    )
    (net (code "106") (name "Net-(Q1-B)") (class "Default")
      (node (ref "Q1") (pin "1") (pinfunction "B_1") (pintype "unspecified"))
      (node (ref "R53") (pin "2") (pinfunction "2_2") (pintype "unspecified"))
    )
    (net (code "107") (name "Net-(Q1-E)") (class "Default")
      (node (ref "Q1") (pin "2") (pinfunction "E_2") (pintype "unspecified"))
      (node (ref "R59") (pin "1") (pinfunction "1_1") (pintype "unspecified"))
      (node (ref "U15") (pin "13") (pinfunction "DTR#_13") (pintype "unspecified"))
    )
    (net (code "108") (name "Net-(Q2-B)") (class "Default")
      (node (ref "Q2") (pin "1") (pinfunction "B_1") (pintype "unspecified"))
      (node (ref "R59") (pin "2") (pinfunction "2_2") (pintype "unspecified"))
    )
    (net (code "109") (name "Net-(Q2-E)") (class "Default")
      (node (ref "Q2") (pin "2") (pinfunction "E_2") (pintype "unspecified"))
      (node (ref "R53") (pin "1") (pinfunction "1_1") (pintype "unspecified"))
      (node (ref "U15") (pin "14") (pinfunction "RTS#_14") (pintype "unspecified"))
    )
    (net (code "110") (name "Net-(R14-Pad2)") (class "Default")
      (node (ref "R14") (pin "2") (pinfunction "2_2") (pintype "unspecified"))
      (node (ref "U5") (pin "1") (pinfunction "1_1") (pintype "unspecified"))
    )
    (net (code "111") (name "Net-(R33-Pad2)") (class "Default")
      (node (ref "R33") (pin "2") (pinfunction "2_2") (pintype "unspecified"))
      (node (ref "U10") (pin "1") (pinfunction "1_1") (pintype "unspecified"))
    )
    (net (code "112") (name "Net-(U2-ON{slash}OFF)") (class "Default")
      (node (ref "R9") (pin "1") (pinfunction "1_1") (pintype "unspecified"))
      (node (ref "U2") (pin "4") (pinfunction "ON/OFF_4") (pintype "input"))
    )
    (net (code "113") (name "Net-(U2-OUTPUT)") (class "Default")
      (node (ref "D2") (pin "2") (pinfunction "2_2") (pintype "input"))
      (node (ref "L1") (pin "2") (pinfunction "2_2") (pintype "unspecified"))
      (node (ref "U2") (pin "2") (pinfunction "OUTPUT_2") (pintype "input"))
    )
    (net (code "114") (name "Net-(U6-Q7S)") (class "Default")
      (node (ref "U6") (pin "9") (pinfunction "Q7S_9") (pintype "unspecified"))
      (node (ref "U8") (pin "14") (pinfunction "DS_14") (pintype "unspecified"))
    )
    (net (code "115") (name "Net-(U11-C1+)") (class "Default")
      (node (ref "C25") (pin "2") (pinfunction "2_2") (pintype "unspecified"))
      (node (ref "U11") (pin "1") (pinfunction "C1+_1") (pintype "unspecified"))
    )
    (net (code "116") (name "Net-(U11-C1-)") (class "Default")
      (node (ref "C25") (pin "1") (pinfunction "1_1") (pintype "unspecified"))
      (node (ref "U11") (pin "3") (pinfunction "C1-_3") (pintype "unspecified"))
    )
    (net (code "117") (name "Net-(U11-C2+)") (class "Default")
      (node (ref "C27") (pin "2") (pinfunction "2_2") (pintype "unspecified"))
      (node (ref "U11") (pin "4") (pinfunction "C2+_4") (pintype "unspecified"))
    )
    (net (code "118") (name "Net-(U11-C2-)") (class "Default")
      (node (ref "C27") (pin "1") (pinfunction "1_1") (pintype "unspecified"))
      (node (ref "U11") (pin "5") (pinfunction "C2-_5") (pintype "unspecified"))
    )
    (net (code "119") (name "Net-(U11-V+)") (class "Default")
      (node (ref "C24") (pin "2") (pinfunction "2_2") (pintype "unspecified"))
      (node (ref "U11") (pin "2") (pinfunction "V+_2") (pintype "unspecified"))
    )
    (net (code "120") (name "Net-(U11-V-)") (class "Default")
      (node (ref "C28") (pin "1") (pinfunction "1_1") (pintype "unspecified"))
      (node (ref "U11") (pin "6") (pinfunction "V-_6") (pintype "unspecified"))
    )
    (net (code "121") (name "Net-(U15-UD+)") (class "Default")
      (node (ref "U15") (pin "5") (pinfunction "UD+_5") (pintype "unspecified"))
      (node (ref "U17") (pin "6") (pinfunction "6_6") (pintype "unspecified"))
    )
    (net (code "122") (name "Net-(U15-UD-)") (class "Default")
      (node (ref "U15") (pin "6") (pinfunction "UD-_6") (pintype "unspecified"))
      (node (ref "U17") (pin "4") (pinfunction "4_4") (pintype "unspecified"))
    )
    (net (code "123") (name "Net-(U15-V3)") (class "Default")
      (node (ref "C35") (pin "1") (pinfunction "1_1") (pintype "unspecified"))
      (node (ref "U15") (pin "4") (pinfunction "V3_4") (pintype "unspecified"))
    )
    (net (code "124") (name "Net-(U15-XI)") (class "Default")
      (node (ref "C36") (pin "1") (pinfunction "1_1") (pintype "unspecified"))
      (node (ref "U15") (pin "7") (pinfunction "XI_7") (pintype "unspecified"))
      (node (ref "Y1") (pin "2") (pinfunction "OSC2_2") (pintype "unspecified"))
    )
    (net (code "125") (name "Net-(U15-XO)") (class "Default")
      (node (ref "C37") (pin "1") (pinfunction "1_1") (pintype "unspecified"))
      (node (ref "U15") (pin "8") (pinfunction "XO_8") (pintype "unspecified"))
      (node (ref "Y1") (pin "1") (pinfunction "OSC1_1") (pintype "unspecified"))
    )
    (net (code "126") (name "VIN_12V") (class "Default")
      (node (ref "C2") (pin "1") (pintype "unspecified"))
      (node (ref "C4") (pin "2") (pinfunction "2_2") (pintype "unspecified"))
      (node (ref "D1") (pin "2") (pinfunction "2_2") (pintype "unspecified"))
      (node (ref "U2") (pin "1") (pinfunction "VIN_1") (pintype "input"))
    )
    (net (code "127") (name "VUSB") (class "Default")
      (node (ref "D15") (pin "2") (pinfunction "A_2") (pintype "input"))
      (node (ref "P23") (pin "1") (pinfunction "VBUS_1") (pintype "unspecified"))
      (node (ref "U17") (pin "5") (pinfunction "5_5") (pintype "unspecified"))
    )
    (net (code "128") (name "unconnected-(P19-Pad1)") (class "Default")
      (node (ref "P19") (pin "1") (pinfunction "1_1") (pintype "unspecified+no_connect"))
    )
    (net (code "129") (name "unconnected-(P20-Pad2)") (class "Default")
      (node (ref "P20") (pin "2") (pinfunction "2_2") (pintype "unspecified+no_connect"))
    )
    (net (code "130") (name "unconnected-(U4-NC-Pad1)") (class "Default")
      (node (ref "U4") (pin "1") (pinfunction "NC_1") (pintype "unspecified"))
    )
    (net (code "131") (name "unconnected-(U7-NC-Pad1)") (class "Default")
      (node (ref "U7") (pin "1") (pinfunction "NC_1") (pintype "unspecified"))
    )
    (net (code "132") (name "unconnected-(U8-Q7S-Pad9)") (class "Default")
      (node (ref "U8") (pin "9") (pinfunction "Q7S_9") (pintype "unspecified"))
    )
    (net (code "133") (name "unconnected-(U9-CLK-Pad20)") (class "Default")
      (node (ref "U9") (pin "20") (pinfunction "CLK_20") (pintype "unspecified"))
    )
    (net (code "134") (name "unconnected-(U9-CMD-Pad19)") (class "Default")
      (node (ref "U9") (pin "19") (pinfunction "CMD_19") (pintype "unspecified"))
    )
    (net (code "135") (name "unconnected-(U9-NC-Pad32)") (class "Default")
      (node (ref "U9") (pin "32") (pinfunction "NC_32") (pintype "unspecified"))
    )
    (net (code "136") (name "unconnected-(U9-SD0-Pad21)") (class "Default")
      (node (ref "U9") (pin "21") (pinfunction "SD0_21") (pintype "unspecified"))
    )
    (net (code "137") (name "unconnected-(U9-SD1-Pad22)") (class "Default")
      (node (ref "U9") (pin "22") (pinfunction "SD1_22") (pintype "unspecified"))
    )
    (net (code "138") (name "unconnected-(U9-SD2-Pad17)") (class "Default")
      (node (ref "U9") (pin "17") (pinfunction "SD2_17") (pintype "unspecified"))
    )
    (net (code "139") (name "unconnected-(U9-SD3-Pad18)") (class "Default")
      (node (ref "U9") (pin "18") (pinfunction "SD3_18") (pintype "unspecified"))
    )
    (net (code "140") (name "unconnected-(U12-NC-Pad1)") (class "Default")
      (node (ref "U12") (pin "1") (pinfunction "NC_1") (pintype "unspecified"))
    )
    (net (code "141") (name "unconnected-(U13-NC-Pad1)") (class "Default")
      (node (ref "U13") (pin "1") (pinfunction "NC_1") (pintype "unspecified"))
    )
    (net (code "142") (name "unconnected-(U14-NC-Pad1)") (class "Default")
      (node (ref "U14") (pin "1") (pinfunction "NC_1") (pintype "unspecified"))
    )
    (net (code "143") (name "unconnected-(U15-CTS#-Pad9)") (class "Default")
      (node (ref "U15") (pin "9") (pinfunction "CTS#_9") (pintype "unspecified"))
    )
    (net (code "144") (name "unconnected-(U15-DCD#-Pad12)") (class "Default")
      (node (ref "U15") (pin "12") (pinfunction "DCD#_12") (pintype "unspecified"))
    )
    (net (code "145") (name "unconnected-(U15-DSR#-Pad10)") (class "Default")
      (node (ref "U15") (pin "10") (pinfunction "DSR#_10") (pintype "unspecified"))
    )
    (net (code "146") (name "unconnected-(U15-R232-Pad15)") (class "Default")
      (node (ref "U15") (pin "15") (pinfunction "R232_15") (pintype "unspecified"))
    )
    (net (code "147") (name "unconnected-(U15-RI#-Pad11)") (class "Default")
      (node (ref "U15") (pin "11") (pinfunction "RI#_11") (pintype "unspecified"))
    )
    (net (code "148") (name "unconnected-(U16-DAT1-Pad8)") (class "Default")
      (node (ref "U16") (pin "8") (pinfunction "DAT1_8") (pintype "unspecified"))
    )
    (net (code "149") (name "unconnected-(U16-DAT2-Pad1)") (class "Default")
      (node (ref "U16") (pin "1") (pinfunction "DAT2_1") (pintype "unspecified"))
    )
  )
)
